# MAIN.net
KiCad netlist of a schematic drawn in Altium Designer
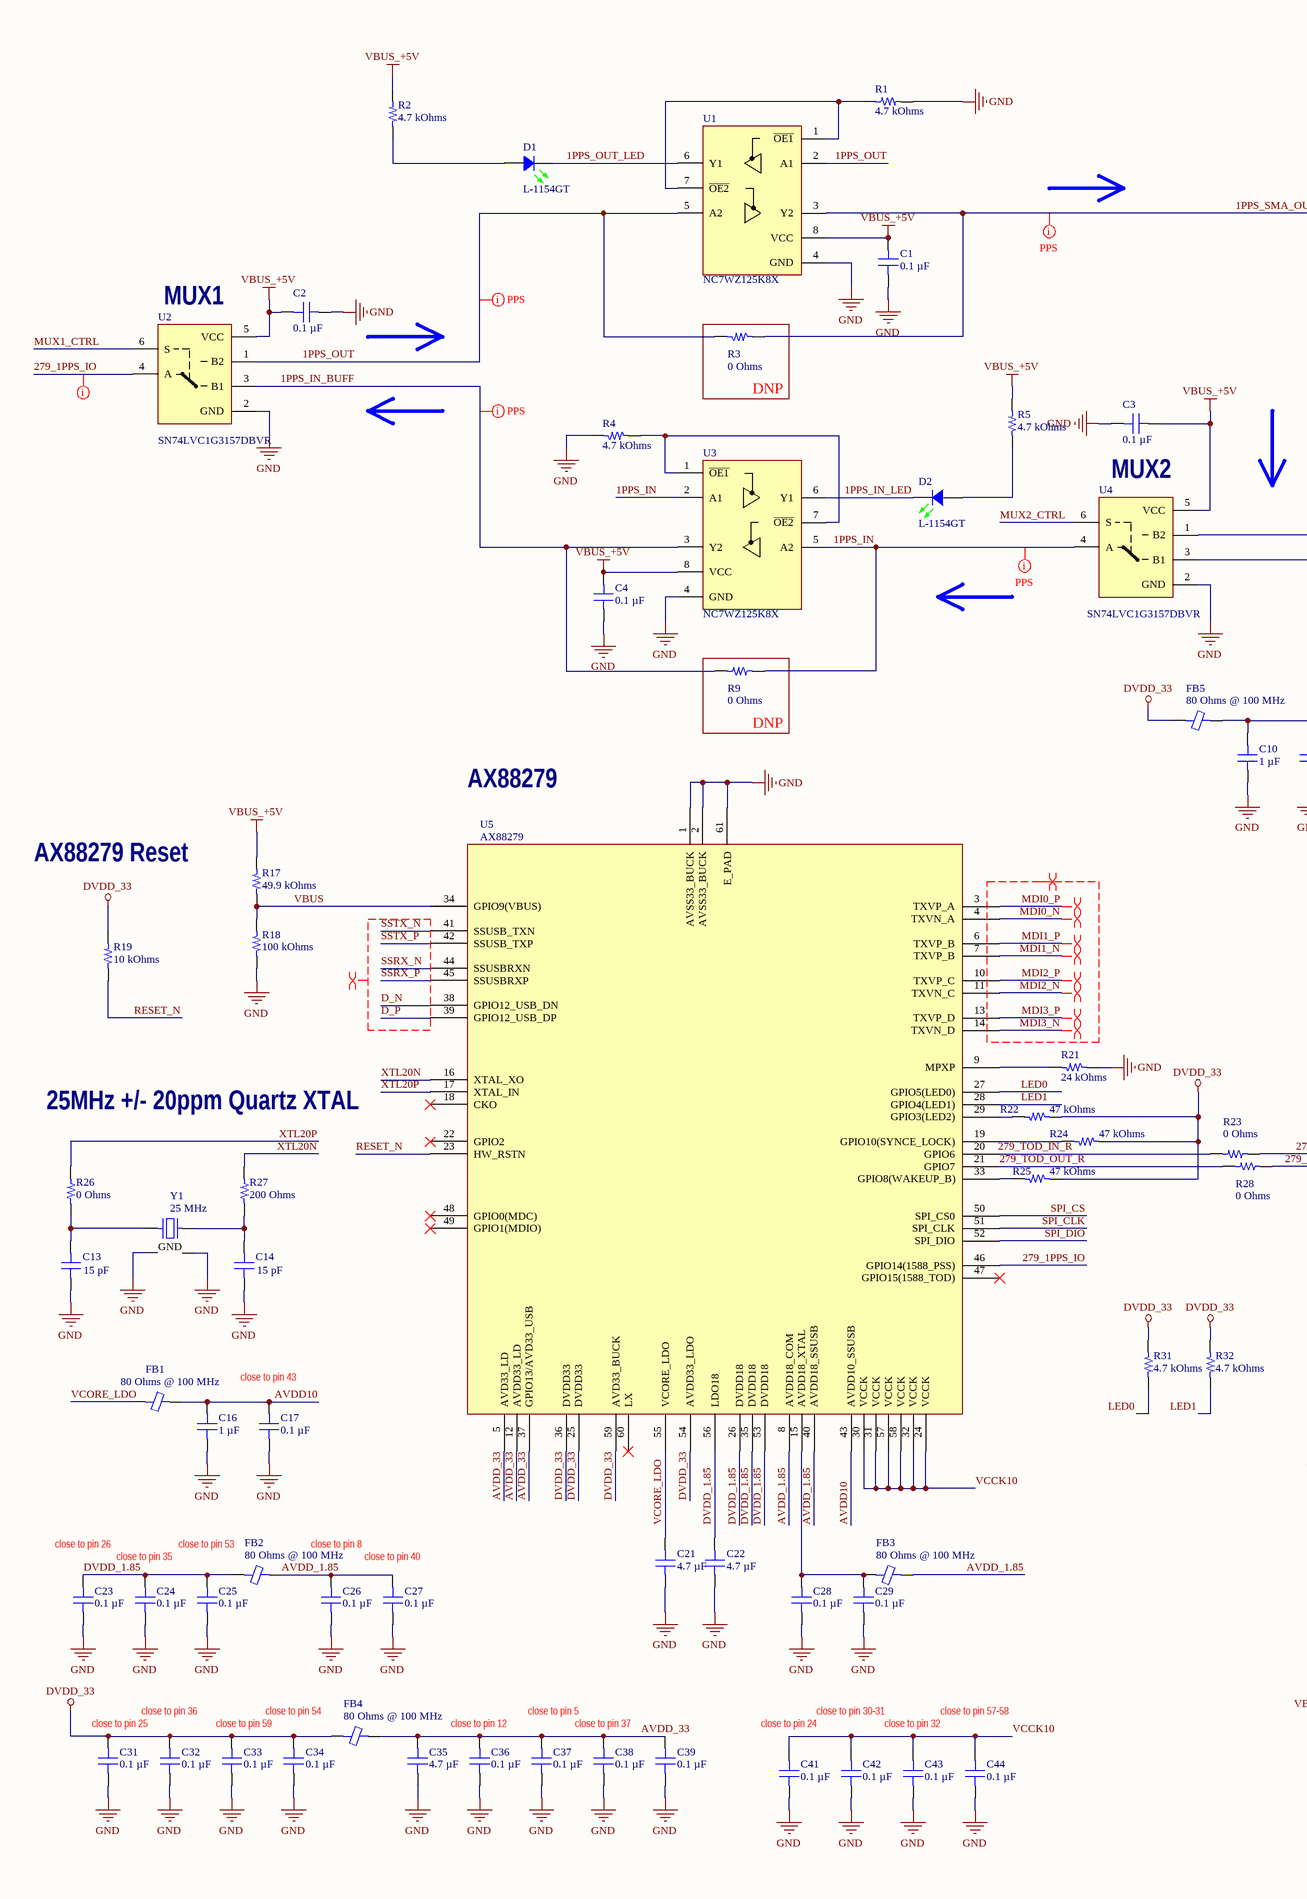
[diagram p0: MAIN.SchDoc, left]
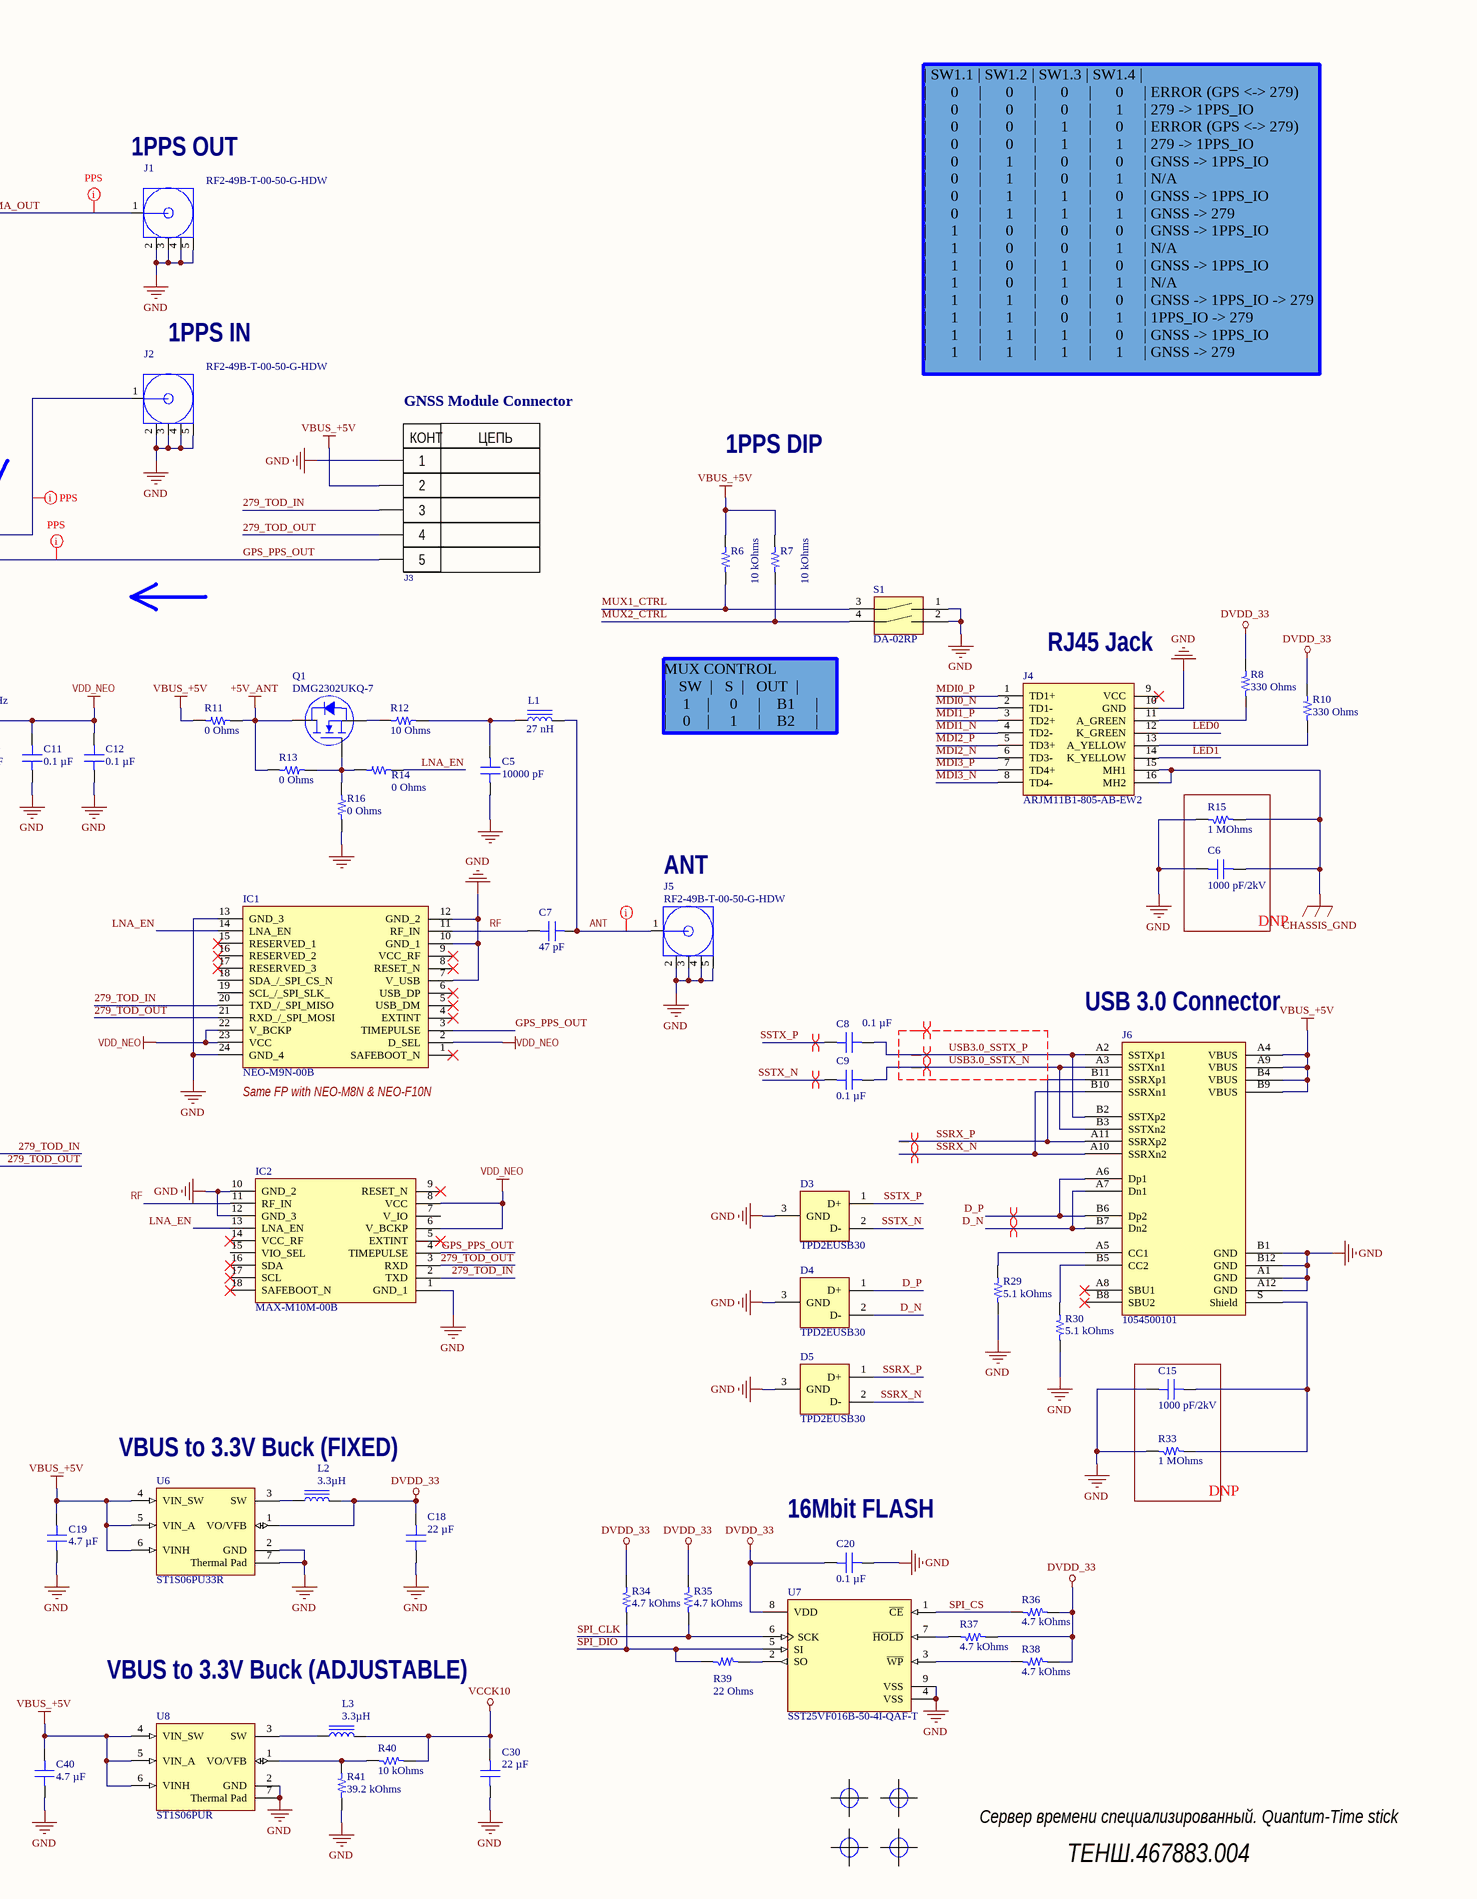
[diagram p1: MAIN.SchDoc, right]

(export (version "E")
  (design (tool "Eeschema 10.0.6"))
  (components
    (comp (ref "C1")
      (value "0.1 µF")
      (footprint "CAP 0402_1005")
      (description "CAP CER 0.1UF 10V X7R 0402")
      (fields (field (name "TOLERANCE") "±10%") (field (name "MANUFACTURER") "Yageo"))
      (libsource (lib "Celestial Altium Library - altium_library") (part "Capacitor"))
    )
    (comp (ref "C2")
      (value "0.1 µF")
      (footprint "CAP 0402_1005")
      (description "CAP CER 0.1UF 10V X7R 0402")
      (fields (field (name "TOLERANCE") "±10%") (field (name "MANUFACTURER") "Yageo"))
      (libsource (lib "Celestial Altium Library - altium_library") (part "Capacitor"))
    )
    (comp (ref "C3")
      (value "0.1 µF")
      (footprint "CAP 0402_1005")
      (description "CAP CER 0.1UF 10V X7R 0402")
      (fields (field (name "TOLERANCE") "±10%") (field (name "MANUFACTURER") "Yageo"))
      (libsource (lib "Celestial Altium Library - altium_library") (part "Capacitor"))
    )
    (comp (ref "C4")
      (value "0.1 µF")
      (footprint "CAP 0402_1005")
      (description "CAP CER 0.1UF 10V X7R 0402")
      (fields (field (name "TOLERANCE") "±10%") (field (name "MANUFACTURER") "Yageo"))
      (libsource (lib "Celestial Altium Library - altium_library") (part "Capacitor"))
    )
    (comp (ref "C5")
      (value "10000 pF")
      (footprint "CAP 0402_1005")
      (description "CAP CER 10000PF 50V X7R 0402")
      (fields (field (name "PART NUMBER") "CC0402KRX7R9BB103") (field (name "MANUFACTURER") "Yageo"))
      (libsource (lib "Celestial Altium Library - altium_library") (part "Capacitor"))
    )
    (comp (ref "C6")
      (value "1000 pF/2kV")
      (footprint "CAP 1206_3216 - 0.8MM")
      (description "CAP CER 1000PF 2KV X7R 1206")
      (fields (field (name "PART NUMBER") "CC1206KKX7RDBB102") (field (name "MANUFACTURER") "Yageo"))
      (libsource (lib "Celestial Altium Library - altium_library") (part "Capacitor"))
    )
    (comp (ref "C7")
      (value "47 pF")
      (footprint "CAP 0402_1005")
      (description "CAP CER 47PF 50V C0G/NPO 0402")
      (fields (field (name "MANUFACTURER") "Yageo") (field (name "TOLERANCE") "±10%"))
      (libsource (lib "Celestial Altium Library - altium_library") (part "Capacitor"))
    )
    (comp (ref "C8")
      (value "0.1 µF")
      (footprint "CAP 0402_1005")
      (description "CAP CER 0.1UF 10V X7R 0402")
      (fields (field (name "TOLERANCE") "±10%") (field (name "MANUFACTURER") "Yageo"))
      (libsource (lib "Celestial Altium Library - altium_library") (part "Capacitor"))
    )
    (comp (ref "C9")
      (value "0.1 µF")
      (footprint "CAP 0402_1005")
      (description "CAP CER 0.1UF 10V X7R 0402")
      (fields (field (name "TOLERANCE") "±10%") (field (name "MANUFACTURER") "Yageo"))
      (libsource (lib "Celestial Altium Library - altium_library") (part "Capacitor"))
    )
    (comp (ref "C10")
      (value "1 µF")
      (footprint "CAP 0402_1005")
      (description "CAP CER 1UF 10V X5R 0402")
      (fields (field (name "TOLERANCE") "±10%") (field (name "MANUFACTURER") "Yageo"))
      (libsource (lib "Celestial Altium Library - altium_library") (part "Capacitor"))
    )
    (comp (ref "C11")
      (value "0.1 µF")
      (footprint "CAP 0402_1005")
      (description "CAP CER 0.1UF 10V X7R 0402")
      (fields (field (name "TOLERANCE") "±10%") (field (name "MANUFACTURER") "Yageo"))
      (libsource (lib "Celestial Altium Library - altium_library") (part "Capacitor"))
    )
    (comp (ref "C12")
      (value "0.1 µF")
      (footprint "CAP 0402_1005")
      (description "CAP CER 0.1UF 10V X7R 0402")
      (fields (field (name "TOLERANCE") "±10%") (field (name "MANUFACTURER") "Yageo"))
      (libsource (lib "Celestial Altium Library - altium_library") (part "Capacitor"))
    )
    (comp (ref "C13")
      (value "15 pF")
      (footprint "CAP 0402_1005")
      (description "CAP CER 15PF 50V C0G/NPO 0402")
      (fields (field (name "MANUFACTURER") "Yageo") (field (name "TOLERANCE") "±10%"))
      (libsource (lib "Celestial Altium Library - altium_library") (part "Capacitor"))
    )
    (comp (ref "C14")
      (value "15 pF")
      (footprint "CAP 0402_1005")
      (description "CAP CER 15PF 50V C0G/NPO 0402")
      (fields (field (name "MANUFACTURER") "Yageo") (field (name "TOLERANCE") "±10%"))
      (libsource (lib "Celestial Altium Library - altium_library") (part "Capacitor"))
    )
    (comp (ref "C15")
      (value "1000 pF/2kV")
      (footprint "CAP 1206_3216 - 0.8MM")
      (description "CAP CER 1000PF 2KV X7R 1206")
      (fields (field (name "PART NUMBER") "CC1206KKX7RDBB102") (field (name "MANUFACTURER") "Yageo"))
      (libsource (lib "Celestial Altium Library - altium_library") (part "Capacitor"))
    )
    (comp (ref "C16")
      (value "1 µF")
      (footprint "CAP 0402_1005")
      (description "CAP CER 1UF 10V X5R 0402")
      (fields (field (name "TOLERANCE") "±10%") (field (name "MANUFACTURER") "Yageo"))
      (libsource (lib "Celestial Altium Library - altium_library") (part "Capacitor"))
    )
    (comp (ref "C17")
      (value "0.1 µF")
      (footprint "CAP 0402_1005")
      (description "CAP CER 0.1UF 10V X7R 0402")
      (fields (field (name "TOLERANCE") "±10%") (field (name "MANUFACTURER") "Yageo"))
      (libsource (lib "Celestial Altium Library - altium_library") (part "Capacitor"))
    )
    (comp (ref "C18")
      (value "22 µF")
      (footprint "CAP 0603_1608")
      (description "CAP CER 22UF 10V X5R 0603")
      (fields (field (name "MANUFACTURER") "Yageo") (field (name "TOLERANCE") "±20%"))
      (libsource (lib "Celestial Altium Library - altium_library") (part "Capacitor"))
    )
    (comp (ref "C19")
      (value "4.7 µF")
      (footprint "CAP 0402_1005")
      (description "CAP CER 4.7UF 10V X5R 0402")
      (fields (field (name "TOLERANCE") "±20%") (field (name "MANUFACTURER") "Yageo"))
      (libsource (lib "Celestial Altium Library - altium_library") (part "Capacitor"))
    )
    (comp (ref "C20")
      (value "0.1 µF")
      (footprint "CAP 0402_1005")
      (description "CAP CER 0.1UF 10V X7R 0402")
      (fields (field (name "TOLERANCE") "±10%") (field (name "MANUFACTURER") "Yageo"))
      (libsource (lib "Celestial Altium Library - altium_library") (part "Capacitor"))
    )
    (comp (ref "C21")
      (value "4.7 µF")
      (footprint "CAP 0402_1005")
      (description "CAP CER 4.7UF 10V X5R 0402")
      (fields (field (name "TOLERANCE") "±20%") (field (name "MANUFACTURER") "Yageo"))
      (libsource (lib "Celestial Altium Library - altium_library") (part "Capacitor"))
    )
    (comp (ref "C22")
      (value "4.7 µF")
      (footprint "CAP 0402_1005")
      (description "CAP CER 4.7UF 10V X5R 0402")
      (fields (field (name "TOLERANCE") "±20%") (field (name "MANUFACTURER") "Yageo"))
      (libsource (lib "Celestial Altium Library - altium_library") (part "Capacitor"))
    )
    (comp (ref "C23")
      (value "0.1 µF")
      (footprint "CAP 0402_1005")
      (description "CAP CER 0.1UF 10V X7R 0402")
      (fields (field (name "TOLERANCE") "±10%") (field (name "MANUFACTURER") "Yageo"))
      (libsource (lib "Celestial Altium Library - altium_library") (part "Capacitor"))
    )
    (comp (ref "C24")
      (value "0.1 µF")
      (footprint "CAP 0402_1005")
      (description "CAP CER 0.1UF 10V X7R 0402")
      (fields (field (name "TOLERANCE") "±10%") (field (name "MANUFACTURER") "Yageo"))
      (libsource (lib "Celestial Altium Library - altium_library") (part "Capacitor"))
    )
    (comp (ref "C25")
      (value "0.1 µF")
      (footprint "CAP 0402_1005")
      (description "CAP CER 0.1UF 10V X7R 0402")
      (fields (field (name "TOLERANCE") "±10%") (field (name "MANUFACTURER") "Yageo"))
      (libsource (lib "Celestial Altium Library - altium_library") (part "Capacitor"))
    )
    (comp (ref "C26")
      (value "0.1 µF")
      (footprint "CAP 0402_1005")
      (description "CAP CER 0.1UF 10V X7R 0402")
      (fields (field (name "TOLERANCE") "±10%") (field (name "MANUFACTURER") "Yageo"))
      (libsource (lib "Celestial Altium Library - altium_library") (part "Capacitor"))
    )
    (comp (ref "C27")
      (value "0.1 µF")
      (footprint "CAP 0402_1005")
      (description "CAP CER 0.1UF 10V X7R 0402")
      (fields (field (name "TOLERANCE") "±10%") (field (name "MANUFACTURER") "Yageo"))
      (libsource (lib "Celestial Altium Library - altium_library") (part "Capacitor"))
    )
    (comp (ref "C28")
      (value "0.1 µF")
      (footprint "CAP 0402_1005")
      (description "CAP CER 0.1UF 10V X7R 0402")
      (fields (field (name "TOLERANCE") "±10%") (field (name "MANUFACTURER") "Yageo"))
      (libsource (lib "Celestial Altium Library - altium_library") (part "Capacitor"))
    )
    (comp (ref "C29")
      (value "0.1 µF")
      (footprint "CAP 0402_1005")
      (description "CAP CER 0.1UF 10V X7R 0402")
      (fields (field (name "TOLERANCE") "±10%") (field (name "MANUFACTURER") "Yageo"))
      (libsource (lib "Celestial Altium Library - altium_library") (part "Capacitor"))
    )
    (comp (ref "C30")
      (value "22 µF")
      (footprint "CAP 0603_1608")
      (description "CAP CER 22UF 10V X5R 0603")
      (fields (field (name "MANUFACTURER") "Yageo") (field (name "TOLERANCE") "±20%"))
      (libsource (lib "Celestial Altium Library - altium_library") (part "Capacitor"))
    )
    (comp (ref "C31")
      (value "0.1 µF")
      (footprint "CAP 0402_1005")
      (description "CAP CER 0.1UF 10V X7R 0402")
      (fields (field (name "TOLERANCE") "±10%") (field (name "MANUFACTURER") "Yageo"))
      (libsource (lib "Celestial Altium Library - altium_library") (part "Capacitor"))
    )
    (comp (ref "C32")
      (value "0.1 µF")
      (footprint "CAP 0402_1005")
      (description "CAP CER 0.1UF 10V X7R 0402")
      (fields (field (name "TOLERANCE") "±10%") (field (name "MANUFACTURER") "Yageo"))
      (libsource (lib "Celestial Altium Library - altium_library") (part "Capacitor"))
    )
    (comp (ref "C33")
      (value "0.1 µF")
      (footprint "CAP 0402_1005")
      (description "CAP CER 0.1UF 10V X7R 0402")
      (fields (field (name "TOLERANCE") "±10%") (field (name "MANUFACTURER") "Yageo"))
      (libsource (lib "Celestial Altium Library - altium_library") (part "Capacitor"))
    )
    (comp (ref "C34")
      (value "0.1 µF")
      (footprint "CAP 0402_1005")
      (description "CAP CER 0.1UF 10V X7R 0402")
      (fields (field (name "TOLERANCE") "±10%") (field (name "MANUFACTURER") "Yageo"))
      (libsource (lib "Celestial Altium Library - altium_library") (part "Capacitor"))
    )
    (comp (ref "C35")
      (value "4.7 µF")
      (footprint "CAP 0402_1005")
      (description "CAP CER 4.7UF 10V X5R 0402")
      (fields (field (name "TOLERANCE") "±20%") (field (name "MANUFACTURER") "Yageo"))
      (libsource (lib "Celestial Altium Library - altium_library") (part "Capacitor"))
    )
    (comp (ref "C36")
      (value "0.1 µF")
      (footprint "CAP 0402_1005")
      (description "CAP CER 0.1UF 10V X7R 0402")
      (fields (field (name "TOLERANCE") "±10%") (field (name "MANUFACTURER") "Yageo"))
      (libsource (lib "Celestial Altium Library - altium_library") (part "Capacitor"))
    )
    (comp (ref "C37")
      (value "0.1 µF")
      (footprint "CAP 0402_1005")
      (description "CAP CER 0.1UF 10V X7R 0402")
      (fields (field (name "TOLERANCE") "±10%") (field (name "MANUFACTURER") "Yageo"))
      (libsource (lib "Celestial Altium Library - altium_library") (part "Capacitor"))
    )
    (comp (ref "C38")
      (value "0.1 µF")
      (footprint "CAP 0402_1005")
      (description "CAP CER 0.1UF 10V X7R 0402")
      (fields (field (name "TOLERANCE") "±10%") (field (name "MANUFACTURER") "Yageo"))
      (libsource (lib "Celestial Altium Library - altium_library") (part "Capacitor"))
    )
    (comp (ref "C39")
      (value "0.1 µF")
      (footprint "CAP 0402_1005")
      (description "CAP CER 0.1UF 10V X7R 0402")
      (fields (field (name "TOLERANCE") "±10%") (field (name "MANUFACTURER") "Yageo"))
      (libsource (lib "Celestial Altium Library - altium_library") (part "Capacitor"))
    )
    (comp (ref "C40")
      (value "4.7 µF")
      (footprint "CAP 0402_1005")
      (description "CAP CER 4.7UF 10V X5R 0402")
      (fields (field (name "TOLERANCE") "±20%") (field (name "MANUFACTURER") "Yageo"))
      (libsource (lib "Celestial Altium Library - altium_library") (part "Capacitor"))
    )
    (comp (ref "C41")
      (value "0.1 µF")
      (footprint "CAP 0402_1005")
      (description "CAP CER 0.1UF 10V X7R 0402")
      (fields (field (name "TOLERANCE") "±10%") (field (name "MANUFACTURER") "Yageo"))
      (libsource (lib "Celestial Altium Library - altium_library") (part "Capacitor"))
    )
    (comp (ref "C42")
      (value "0.1 µF")
      (footprint "CAP 0402_1005")
      (description "CAP CER 0.1UF 10V X7R 0402")
      (fields (field (name "TOLERANCE") "±10%") (field (name "MANUFACTURER") "Yageo"))
      (libsource (lib "Celestial Altium Library - altium_library") (part "Capacitor"))
    )
    (comp (ref "C43")
      (value "0.1 µF")
      (footprint "CAP 0402_1005")
      (description "CAP CER 0.1UF 10V X7R 0402")
      (fields (field (name "TOLERANCE") "±10%") (field (name "MANUFACTURER") "Yageo"))
      (libsource (lib "Celestial Altium Library - altium_library") (part "Capacitor"))
    )
    (comp (ref "C44")
      (value "0.1 µF")
      (footprint "CAP 0402_1005")
      (description "CAP CER 0.1UF 10V X7R 0402")
      (fields (field (name "TOLERANCE") "±10%") (field (name "MANUFACTURER") "Yageo"))
      (libsource (lib "Celestial Altium Library - altium_library") (part "Capacitor"))
    )
    (comp (ref "D1")
      (value "L-1154GT")
      (footprint "SamacSys:LED_3MM_GREEN")
      (description "LED, 3mm, Green")
      (libsource (lib "SamacSys") (part "L-1154GT"))
    )
    (comp (ref "D2")
      (value "L-1154GT")
      (footprint "SamacSys:LED_3MM_GREEN")
      (description "LED, 3mm, Green")
      (libsource (lib "SamacSys") (part "L-1154GT"))
    )
    (comp (ref "D3")
      (value "TPD2EUSB30")
      (footprint "SamacSys:SOT35P100X50-3N")
      (description "TVS DIODE 3.6VWM 8VC SOT3")
      (fields
        (field (name "MANUFACTURER_PART_NUMBER") "TPD2EUSB30ADRTR")
        (field (name "MOUSER PART NUMBER") "595-TPD2EUSB30ADRTR")
      )
      (libsource (lib "SamacSys") (part "TPD2EUSB30ADRTR"))
    )
    (comp (ref "D4")
      (value "TPD2EUSB30")
      (footprint "SamacSys:SOT35P100X50-3N")
      (description "TVS DIODE 3.6VWM 8VC SOT3")
      (fields
        (field (name "MANUFACTURER_PART_NUMBER") "TPD2EUSB30ADRTR")
        (field (name "MOUSER PART NUMBER") "595-TPD2EUSB30ADRTR")
      )
      (libsource (lib "SamacSys") (part "TPD2EUSB30ADRTR"))
    )
    (comp (ref "D5")
      (value "TPD2EUSB30")
      (footprint "SamacSys:SOT35P100X50-3N")
      (description "TVS DIODE 3.6VWM 8VC SOT3")
      (fields
        (field (name "MANUFACTURER_PART_NUMBER") "TPD2EUSB30ADRTR")
        (field (name "MOUSER PART NUMBER") "595-TPD2EUSB30ADRTR")
      )
      (libsource (lib "SamacSys") (part "TPD2EUSB30ADRTR"))
    )
    (comp (ref "FB1")
      (value "80 Ohms @ 100 MHz")
      (footprint "FER 0402_1005")
      (description "FERRITE BEAD 80 OHM 0402 1LN")
      (fields
        (field (name "MANUFACTURER") "Murata Electronics")
        (field (name "PART NUMBER") "BLM15PD800SN1D")
      )
      (libsource (lib "Celestial Altium Library - altium_library") (part "Ferrite Chip"))
    )
    (comp (ref "FB2")
      (value "80 Ohms @ 100 MHz")
      (footprint "FER 0402_1005")
      (description "FERRITE BEAD 80 OHM 0402 1LN")
      (fields
        (field (name "MANUFACTURER") "Murata Electronics")
        (field (name "PART NUMBER") "BLM15PD800SN1D")
      )
      (libsource (lib "Celestial Altium Library - altium_library") (part "Ferrite Chip"))
    )
    (comp (ref "FB3")
      (value "80 Ohms @ 100 MHz")
      (footprint "FER 0402_1005")
      (description "FERRITE BEAD 80 OHM 0402 1LN")
      (fields
        (field (name "MANUFACTURER") "Murata Electronics")
        (field (name "PART NUMBER") "BLM15PD800SN1D")
      )
      (libsource (lib "Celestial Altium Library - altium_library") (part "Ferrite Chip"))
    )
    (comp (ref "FB4")
      (value "80 Ohms @ 100 MHz")
      (footprint "FER 0402_1005")
      (description "FERRITE BEAD 80 OHM 0402 1LN")
      (fields
        (field (name "MANUFACTURER") "Murata Electronics")
        (field (name "PART NUMBER") "BLM15PD800SN1D")
      )
      (libsource (lib "Celestial Altium Library - altium_library") (part "Ferrite Chip"))
    )
    (comp (ref "FB5")
      (value "80 Ohms @ 100 MHz")
      (footprint "FER 0402_1005")
      (description "FERRITE BEAD 80 OHM 0402 1LN")
      (fields
        (field (name "MANUFACTURER") "Murata Electronics")
        (field (name "PART NUMBER") "BLM15PD800SN1D")
      )
      (libsource (lib "Celestial Altium Library - altium_library") (part "Ferrite Chip"))
    )
    (comp (ref "IC1")
      (value "NEO-M9N-00B")
      (footprint "SamacSys:NEOM9N00B")
      (description "Integrated Circuit")
      (fields (field (name "MOUSER PART NUMBER") "377-NEO-M9N-00B"))
      (libsource (lib "SamacSys") (part "NEO-M9N-00B"))
    )
    (comp (ref "IC2")
      (value "MAX-M10M-00B")
      (footprint "MAXM10M00B")
      (description "Integrated Circuit")
      (fields (field (name "MOUSER PART NUMBER") "377-MAX-M10M-00B"))
      (libsource (lib "SamacSys") (part "MAX-M10M-00B"))
    )
    (comp (ref "J1")
      (value "RF2-49B-T-00-50-G-HDW")
      (footprint "SamacSys:RF249BT0050GHDW")
      (description "Connector")
      (libsource (lib "SamacSys") (part "RF2-49B-T-00-50-G-HDW"))
    )
    (comp (ref "J2")
      (value "RF2-49B-T-00-50-G-HDW")
      (footprint "SamacSys:RF249BT0050GHDW")
      (description "Connector")
      (libsource (lib "SamacSys") (part "RF2-49B-T-00-50-G-HDW"))
    )
    (comp (ref "J3")
      (value "PBS-5")
      (footprint "SamacSys:PBS-5")
      (description "Connector")
      (fields (field (name "MANUFACTURER") "Connfly") (field (name "PART NUMBER") "PBD-5"))
      (libsource (lib "SamacSys") (part "PBS-5"))
    )
    (comp (ref "J4")
      (value "ARJM11B1-805-AB-EW2")
      (footprint "SamacSys:ARJM11B1805ABEW2")
      (description "Connector")
      (fields (field (name "MOUSER PART NUMBER") "815-RJM11B1805ABEW2"))
      (libsource (lib "SamacSys") (part "ARJM11B1-805-AB-EW2"))
    )
    (comp (ref "J5")
      (value "RF2-49B-T-00-50-G-HDW")
      (footprint "SamacSys:RF249BT0050GHDW")
      (description "Connector")
      (libsource (lib "SamacSys") (part "RF2-49B-T-00-50-G-HDW"))
    )
    (comp (ref "J6")
      (value "1054500101")
      (footprint "Molex 1054500101")
      (description "CONN RCP USB3.1 TYPEC 24P SMD RA")
      (fields (field (name "MANUFACTURER") "Molex"))
      (libsource (lib "Celestial Altium Library - altium_library") (part "USB 3.0 Type C"))
    )
    (comp (ref "L1")
      (value "27 nH")
      (footprint "Murata LQG15 0402")
      (description "FIXED IND 27NH 350MA 0.46OHM SMD")
      (fields
        (field (name "PART NUMBER") "LQG15HS27NJ02D")
        (field (name "MANUFACTURER") "Murata Electronics")
      )
      (libsource (lib "Celestial Altium Library - altium_library") (part "Inductor"))
    )
    (comp (ref "L2")
      (value "3.3µH")
      (footprint "IND 1008_2520")
      (description "FIXED IND 3.3UH 1.2A 100 MOHM")
      (fields (field (name "TOLERANCE") "±20%") (field (name "MANUFACTURER") "Murata Electronics"))
      (libsource (lib "Celestial Altium Library - altium_library") (part "Inductor"))
    )
    (comp (ref "L3")
      (value "3.3µH")
      (footprint "IND 1008_2520")
      (description "FIXED IND 3.3UH 1.2A 100 MOHM")
      (fields (field (name "TOLERANCE") "±20%") (field (name "MANUFACTURER") "Murata Electronics"))
      (libsource (lib "Celestial Altium Library - altium_library") (part "Inductor"))
    )
    (comp (ref "MNT1")
      (value "MOUNT_HOLE")
      (footprint "SamacSys:MOUNT_3mm")
      (description "Mount hole")
      (libsource (lib "SamacSys") (part "MOUNT_HOLE"))
    )
    (comp (ref "MNT2")
      (value "MOUNT_HOLE")
      (footprint "SamacSys:MOUNT_3mm")
      (description "Mount hole")
      (libsource (lib "SamacSys") (part "MOUNT_HOLE"))
    )
    (comp (ref "MNT3")
      (value "MOUNT_HOLE")
      (footprint "SamacSys:MOUNT_3mm")
      (description "Mount hole")
      (libsource (lib "SamacSys") (part "MOUNT_HOLE"))
    )
    (comp (ref "MNT4")
      (value "MOUNT_HOLE")
      (footprint "SamacSys:MOUNT_3mm")
      (description "Mount hole")
      (libsource (lib "SamacSys") (part "MOUNT_HOLE"))
    )
    (comp (ref "Q1")
      (value "DMG2302UKQ-7")
      (footprint "DIODES SOT-23-3")
      (description "MOSFET BVDSS: 8V-24V SOT23 T&R 3")
      (fields (field (name "MANUFACTURER") "Diodes Incorporated"))
      (libsource (lib "Celestial Altium Library - altium_library") (part "DIODES INC MOSFET N-CH SOT-23-3"))
    )
    (comp (ref "R1")
      (value "4.7 kOhms")
      (footprint "YAGEO RES 0402_1005")
      (description "RES 4.7K OHM 1% 1/16W 0402")
      (fields (field (name "TOLERANCE") "±1%") (field (name "MANUFACTURER") "Yageo"))
      (libsource (lib "Celestial Altium Library - altium_library") (part "Resistor"))
    )
    (comp (ref "R2")
      (value "4.7 kOhms")
      (footprint "YAGEO RES 0402_1005")
      (description "RES 4.7K OHM 1% 1/16W 0402")
      (fields (field (name "TOLERANCE") "±1%") (field (name "MANUFACTURER") "Yageo"))
      (libsource (lib "Celestial Altium Library - altium_library") (part "Resistor"))
    )
    (comp (ref "R3")
      (value "0 Ohms")
      (footprint "YAGEO RES 0402_1005")
      (description "RES 0 OHM JUMPER 1/16W 0402")
      (fields (field (name "TOLERANCE") "Jumper") (field (name "MANUFACTURER") "Yageo"))
      (libsource (lib "Celestial Altium Library - altium_library") (part "Resistor"))
    )
    (comp (ref "R4")
      (value "4.7 kOhms")
      (footprint "YAGEO RES 0402_1005")
      (description "RES 4.7K OHM 1% 1/16W 0402")
      (fields (field (name "TOLERANCE") "±1%") (field (name "MANUFACTURER") "Yageo"))
      (libsource (lib "Celestial Altium Library - altium_library") (part "Resistor"))
    )
    (comp (ref "R5")
      (value "4.7 kOhms")
      (footprint "YAGEO RES 0402_1005")
      (description "RES 4.7K OHM 1% 1/16W 0402")
      (fields (field (name "TOLERANCE") "±1%") (field (name "MANUFACTURER") "Yageo"))
      (libsource (lib "Celestial Altium Library - altium_library") (part "Resistor"))
    )
    (comp (ref "R6")
      (value "10 kOhms")
      (footprint "YAGEO RES 0402_1005")
      (description "RES 10K OHM 1% 1/16W 0402")
      (fields (field (name "TOLERANCE") "±1%") (field (name "MANUFACTURER") "Yageo"))
      (libsource (lib "Celestial Altium Library - altium_library") (part "Resistor"))
    )
    (comp (ref "R7")
      (value "10 kOhms")
      (footprint "YAGEO RES 0402_1005")
      (description "RES 10K OHM 1% 1/16W 0402")
      (fields (field (name "TOLERANCE") "±1%") (field (name "MANUFACTURER") "Yageo"))
      (libsource (lib "Celestial Altium Library - altium_library") (part "Resistor"))
    )
    (comp (ref "R8")
      (value "330 Ohms")
      (footprint "YAGEO RES 0402_1005")
      (description "RES 330 OHM 1% 1/16W 0402")
      (fields (field (name "TOLERANCE") "±1%") (field (name "MANUFACTURER") "Yageo"))
      (libsource (lib "Celestial Altium Library - altium_library") (part "Resistor"))
    )
    (comp (ref "R9")
      (value "0 Ohms")
      (footprint "YAGEO RES 0402_1005")
      (description "RES 0 OHM JUMPER 1/16W 0402")
      (fields (field (name "TOLERANCE") "Jumper") (field (name "MANUFACTURER") "Yageo"))
      (libsource (lib "Celestial Altium Library - altium_library") (part "Resistor"))
    )
    (comp (ref "R10")
      (value "330 Ohms")
      (footprint "YAGEO RES 0402_1005")
      (description "RES 330 OHM 1% 1/16W 0402")
      (fields (field (name "TOLERANCE") "±1%") (field (name "MANUFACTURER") "Yageo"))
      (libsource (lib "Celestial Altium Library - altium_library") (part "Resistor"))
    )
    (comp (ref "R11")
      (value "0 Ohms")
      (footprint "YAGEO RES 0402_1005")
      (description "RES 0 OHM JUMPER 1/16W 0402")
      (fields (field (name "TOLERANCE") "Jumper") (field (name "MANUFACTURER") "Yageo"))
      (libsource (lib "Celestial Altium Library - altium_library") (part "Resistor"))
    )
    (comp (ref "R12")
      (value "10 Ohms")
      (footprint "YAGEO RES 0603_1608")
      (description "RES 10 OHM 1% 1/10W 0603")
      (fields (field (name "PART NUMBER") "RC0603FR-0710RL") (field (name "MANUFACTURER") "Yageo"))
      (libsource (lib "Celestial Altium Library - altium_library") (part "Resistor"))
    )
    (comp (ref "R13")
      (value "0 Ohms")
      (footprint "YAGEO RES 0402_1005")
      (description "RES 0 OHM JUMPER 1/16W 0402")
      (fields (field (name "TOLERANCE") "Jumper") (field (name "MANUFACTURER") "Yageo"))
      (libsource (lib "Celestial Altium Library - altium_library") (part "Resistor"))
    )
    (comp (ref "R14")
      (value "0 Ohms")
      (footprint "YAGEO RES 0402_1005")
      (description "RES 0 OHM JUMPER 1/16W 0402")
      (fields (field (name "TOLERANCE") "Jumper") (field (name "MANUFACTURER") "Yageo"))
      (libsource (lib "Celestial Altium Library - altium_library") (part "Resistor"))
    )
    (comp (ref "R15")
      (value "1 MOhms")
      (footprint "YAGEO RES 0402_1005")
      (description "RES 1M OHM 1% 1/16W 0402")
      (fields (field (name "TOLERANCE") "±1%") (field (name "MANUFACTURER") "Yageo"))
      (libsource (lib "Celestial Altium Library - altium_library") (part "Resistor"))
    )
    (comp (ref "R16")
      (value "0 Ohms")
      (footprint "YAGEO RES 0402_1005")
      (description "RES 0 OHM JUMPER 1/16W 0402")
      (fields (field (name "TOLERANCE") "Jumper") (field (name "MANUFACTURER") "Yageo"))
      (libsource (lib "Celestial Altium Library - altium_library") (part "Resistor"))
    )
    (comp (ref "R17")
      (value "49.9 kOhms")
      (footprint "YAGEO RES 0402_1005")
      (description "RES 49.9K OHM 1% 1/16W 0402")
      (fields (field (name "TOLERANCE") "±1%") (field (name "MANUFACTURER") "Yageo"))
      (libsource (lib "Celestial Altium Library - altium_library") (part "Resistor"))
    )
    (comp (ref "R18")
      (value "100 kOhms")
      (footprint "YAGEO RES 0402_1005")
      (description "RES 100K OHM 1% 1/16W 0402")
      (fields (field (name "TOLERANCE") "±1%") (field (name "MANUFACTURER") "Yageo"))
      (libsource (lib "Celestial Altium Library - altium_library") (part "Resistor"))
    )
    (comp (ref "R19")
      (value "10 kOhms")
      (footprint "YAGEO RES 0402_1005")
      (description "RES 10K OHM 1% 1/16W 0402")
      (fields (field (name "TOLERANCE") "±1%") (field (name "MANUFACTURER") "Yageo"))
      (libsource (lib "Celestial Altium Library - altium_library") (part "Resistor"))
    )
    (comp (ref "R21")
      (value "24 kOhms")
      (footprint "YAGEO RES 0402_1005")
      (description "RES 24K OHM 1% 1/16W 0402")
      (fields (field (name "TOLERANCE") "±1%") (field (name "MANUFACTURER") "Yageo"))
      (libsource (lib "Celestial Altium Library - altium_library") (part "Resistor"))
    )
    (comp (ref "R22")
      (value "47 kOhms")
      (footprint "YAGEO RES 0402_1005")
      (description "RES 47K OHM 1% 1/16W 0402")
      (fields (field (name "TOLERANCE") "±1%") (field (name "MANUFACTURER") "Yageo"))
      (libsource (lib "Celestial Altium Library - altium_library") (part "Resistor"))
    )
    (comp (ref "R23")
      (value "0 Ohms")
      (footprint "YAGEO RES 0402_1005")
      (description "RES 0 OHM JUMPER 1/16W 0402")
      (fields (field (name "TOLERANCE") "Jumper") (field (name "MANUFACTURER") "Yageo"))
      (libsource (lib "Celestial Altium Library - altium_library") (part "Resistor"))
    )
    (comp (ref "R24")
      (value "47 kOhms")
      (footprint "YAGEO RES 0402_1005")
      (description "RES 47K OHM 1% 1/16W 0402")
      (fields (field (name "TOLERANCE") "±1%") (field (name "MANUFACTURER") "Yageo"))
      (libsource (lib "Celestial Altium Library - altium_library") (part "Resistor"))
    )
    (comp (ref "R25")
      (value "47 kOhms")
      (footprint "YAGEO RES 0402_1005")
      (description "RES 47K OHM 1% 1/16W 0402")
      (fields (field (name "TOLERANCE") "±1%") (field (name "MANUFACTURER") "Yageo"))
      (libsource (lib "Celestial Altium Library - altium_library") (part "Resistor"))
    )
    (comp (ref "R26")
      (value "0 Ohms")
      (footprint "YAGEO RES 0402_1005")
      (description "RES 0 OHM JUMPER 1/16W 0402")
      (fields (field (name "TOLERANCE") "Jumper") (field (name "MANUFACTURER") "Yageo"))
      (libsource (lib "Celestial Altium Library - altium_library") (part "Resistor"))
    )
    (comp (ref "R27")
      (value "200 Ohms")
      (footprint "YAGEO RES 0402_1005")
      (description "RES 200 OHM 1% 1/16W 0402")
      (fields (field (name "MANUFACTURER") "Yageo") (field (name "PART NUMBER") "RC0402FR-07200RL"))
      (libsource (lib "Celestial Altium Library - altium_library") (part "Resistor"))
    )
    (comp (ref "R28")
      (value "0 Ohms")
      (footprint "YAGEO RES 0402_1005")
      (description "RES 0 OHM JUMPER 1/16W 0402")
      (fields (field (name "TOLERANCE") "Jumper") (field (name "MANUFACTURER") "Yageo"))
      (libsource (lib "Celestial Altium Library - altium_library") (part "Resistor"))
    )
    (comp (ref "R29")
      (value "5.1 kOhms")
      (footprint "YAGEO RES 0402_1005")
      (description "RES 5.1K OHM 1% 1/16W 0402")
      (fields (field (name "TOLERANCE") "±1%") (field (name "MANUFACTURER") "Yageo"))
      (libsource (lib "Celestial Altium Library - altium_library") (part "Resistor"))
    )
    (comp (ref "R30")
      (value "5.1 kOhms")
      (footprint "YAGEO RES 0402_1005")
      (description "RES 5.1K OHM 1% 1/16W 0402")
      (fields (field (name "TOLERANCE") "±1%") (field (name "MANUFACTURER") "Yageo"))
      (libsource (lib "Celestial Altium Library - altium_library") (part "Resistor"))
    )
    (comp (ref "R31")
      (value "4.7 kOhms")
      (footprint "YAGEO RES 0402_1005")
      (description "RES 4.7K OHM 1% 1/16W 0402")
      (fields (field (name "TOLERANCE") "±1%") (field (name "MANUFACTURER") "Yageo"))
      (libsource (lib "Celestial Altium Library - altium_library") (part "Resistor"))
    )
    (comp (ref "R32")
      (value "4.7 kOhms")
      (footprint "YAGEO RES 0402_1005")
      (description "RES 4.7K OHM 1% 1/16W 0402")
      (fields (field (name "TOLERANCE") "±1%") (field (name "MANUFACTURER") "Yageo"))
      (libsource (lib "Celestial Altium Library - altium_library") (part "Resistor"))
    )
    (comp (ref "R33")
      (value "1 MOhms")
      (footprint "YAGEO RES 0402_1005")
      (description "RES 1M OHM 1% 1/16W 0402")
      (fields (field (name "TOLERANCE") "±1%") (field (name "MANUFACTURER") "Yageo"))
      (libsource (lib "Celestial Altium Library - altium_library") (part "Resistor"))
    )
    (comp (ref "R34")
      (value "4.7 kOhms")
      (footprint "YAGEO RES 0402_1005")
      (description "RES 4.7K OHM 1% 1/16W 0402")
      (fields (field (name "TOLERANCE") "±1%") (field (name "MANUFACTURER") "Yageo"))
      (libsource (lib "Celestial Altium Library - altium_library") (part "Resistor"))
    )
    (comp (ref "R35")
      (value "4.7 kOhms")
      (footprint "YAGEO RES 0402_1005")
      (description "RES 4.7K OHM 1% 1/16W 0402")
      (fields (field (name "TOLERANCE") "±1%") (field (name "MANUFACTURER") "Yageo"))
      (libsource (lib "Celestial Altium Library - altium_library") (part "Resistor"))
    )
    (comp (ref "R36")
      (value "4.7 kOhms")
      (footprint "YAGEO RES 0402_1005")
      (description "RES 4.7K OHM 1% 1/16W 0402")
      (fields (field (name "TOLERANCE") "±1%") (field (name "MANUFACTURER") "Yageo"))
      (libsource (lib "Celestial Altium Library - altium_library") (part "Resistor"))
    )
    (comp (ref "R37")
      (value "4.7 kOhms")
      (footprint "YAGEO RES 0402_1005")
      (description "RES 4.7K OHM 1% 1/16W 0402")
      (fields (field (name "TOLERANCE") "±1%") (field (name "MANUFACTURER") "Yageo"))
      (libsource (lib "Celestial Altium Library - altium_library") (part "Resistor"))
    )
    (comp (ref "R38")
      (value "4.7 kOhms")
      (footprint "YAGEO RES 0402_1005")
      (description "RES 4.7K OHM 1% 1/16W 0402")
      (fields (field (name "TOLERANCE") "±1%") (field (name "MANUFACTURER") "Yageo"))
      (libsource (lib "Celestial Altium Library - altium_library") (part "Resistor"))
    )
    (comp (ref "R39")
      (value "22 Ohms")
      (footprint "YAGEO RES 0402_1005")
      (description "RES 22 OHM 1% 1/16W 0402")
      (fields (field (name "TOLERANCE") "±1%") (field (name "MANUFACTURER") "Yageo"))
      (libsource (lib "Celestial Altium Library - altium_library") (part "Resistor"))
    )
    (comp (ref "R40")
      (value "10 kOhms")
      (footprint "YAGEO RES 0402_1005")
      (description "RES 10K OHM 1% 1/16W 0402")
      (fields (field (name "TOLERANCE") "±1%") (field (name "MANUFACTURER") "Yageo"))
      (libsource (lib "Celestial Altium Library - altium_library") (part "Resistor"))
    )
    (comp (ref "R41")
      (value "39.2 kOhms")
      (footprint "YAGEO RES 0402_1005")
      (description "RES 39.2K OHM 1% 1/16W 0402")
      (fields (field (name "TOLERANCE") "±1%") (field (name "MANUFACTURER") "Yageo"))
      (libsource (lib "Celestial Altium Library - altium_library") (part "Resistor"))
    )
    (comp (ref "S1")
      (value "DA-02RP")
      (footprint "SamacSys:DA02RP")
      (description "DIP Switch, 2P")
      (libsource (lib "SamacSys") (part "DA-02RP"))
    )
    (comp (ref "U1")
      (value "NC7WZ125K8X")
      (footprint "SamacSys:SOP50P310X90-8N")
      (description "Integrated Circuit")
      (libsource (lib "") (part "NC7WZ125K8X_1"))
    )
    (comp (ref "U2")
      (value "SN74LVC1G3157DBVR")
      (footprint "SamacSys:SOT95P280X145-6N")
      (description "Integrated Circuit")
      (fields (field (name "MOUSER PART NUMBER") "595-SN74LVC1G3157DBV"))
      (libsource (lib "SamacSys") (part "SN74LVC1G3157DBVR"))
    )
    (comp (ref "U3")
      (value "NC7WZ125K8X")
      (footprint "SamacSys:SOP50P310X90-8N")
      (description "Integrated Circuit")
      (libsource (lib "SamacSys") (part "NC7WZ125K8X"))
    )
    (comp (ref "U4")
      (value "SN74LVC1G3157DBVR")
      (footprint "SamacSys:SOT95P280X145-6N")
      (description "Integrated Circuit")
      (fields (field (name "MOUSER PART NUMBER") "595-SN74LVC1G3157DBV"))
      (libsource (lib "SamacSys") (part "SN74LVC1G3157DBVR"))
    )
    (comp (ref "U5")
      (value "AX88279")
      (footprint "IC_AX88279")
      (libsource (lib "LotusSound") (part "IC_AX88279"))
    )
    (comp (ref "U6")
      (value "ST1S06PU33R")
      (footprint "DFN6D_L")
      (fields (field (name "MANUFACTURER") "STMicroelectronics"))
      (libsource (lib "Altium Content Vault") (part "PM-DCDC-ST1S06-IL7"))
    )
    (comp (ref "U7")
      (value "SST25VF016B-50-4I-QAF-T")
      (footprint "FP-C04-452-MFG")
      (libsource (lib "Altium Content Vault") (part "d7313dde12fd16fde488169701056cc"))
    )
    (comp (ref "U8")
      (value "ST1S06PUR")
      (footprint "DFN6D_M")
      (libsource (lib "Altium Content Vault") (part "PM-DCDC-ST1S06-IL7"))
    )
    (comp (ref "Y1")
      (value "25 MHz")
      (footprint "NDK NX3225GA")
      (description "CRYSTAL 25.0000MHZ 8PF SMD")
      (fields
        (field (name "MANUFACTURER") "NDK America, Inc.")
        (field (name "PART NUMBER") "NX3225GA-25.000M-STD-CRG-2")
      )
      (libsource (lib "Celestial Altium Library - altium_library") (part "NDK Crystal NX3225GA"))
    )
  )
  (nets
    (net (code "1") (name "+5V_ANT") (class "Default")
      (node (ref "Q1") (pin "3") (pinfunction "D_3") (pintype "passive"))
      (node (ref "R11") (pin "1") (pinfunction "1_1") (pintype "passive"))
      (node (ref "R13") (pin "2") (pinfunction "2_2") (pintype "passive"))
    )
    (net (code "2") (name "/1PPS_IN") (class "Default")
      (node (ref "R9") (pin "1") (pinfunction "1_1") (pintype "passive"))
      (node (ref "U3") (pin "2") (pinfunction "A1_2") (pintype "passive"))
      (node (ref "U3") (pin "5") (pinfunction "A2_5") (pintype "passive"))
      (node (ref "U4") (pin "4") (pinfunction "A_4") (pintype "passive"))
    )
    (net (code "3") (name "/1PPS_IN_BUFF") (class "Default")
      (node (ref "R9") (pin "2") (pinfunction "2_2") (pintype "passive"))
      (node (ref "U2") (pin "3") (pinfunction "B1_3") (pintype "passive"))
      (node (ref "U3") (pin "3") (pinfunction "Y2_3") (pintype "passive"))
    )
    (net (code "4") (name "/1PPS_IN_LED") (class "Default")
      (node (ref "D2") (pin "C") (pinfunction "C_C") (pintype "passive"))
      (node (ref "U3") (pin "6") (pinfunction "Y1_6") (pintype "passive"))
    )
    (net (code "5") (name "/1PPS_OUT") (class "Default")
      (node (ref "R3") (pin "2") (pinfunction "2_2") (pintype "passive"))
      (node (ref "U1") (pin "2") (pinfunction "A1_2") (pintype "passive"))
      (node (ref "U1") (pin "5") (pinfunction "A2_5") (pintype "passive"))
      (node (ref "U2") (pin "1") (pinfunction "B2_1") (pintype "passive"))
    )
    (net (code "6") (name "/1PPS_OUT_LED") (class "Default")
      (node (ref "D1") (pin "C") (pinfunction "C_C") (pintype "passive"))
      (node (ref "U1") (pin "6") (pinfunction "Y1_6") (pintype "passive"))
    )
    (net (code "7") (name "/1PPS_SMA_OUT") (class "Default")
      (node (ref "J1") (pin "1") (pinfunction "1_1") (pintype "passive"))
      (node (ref "R3") (pin "1") (pinfunction "1_1") (pintype "passive"))
      (node (ref "U1") (pin "3") (pinfunction "Y2_3") (pintype "passive"))
    )
    (net (code "8") (name "/279_1PPS_IO") (class "Default")
      (node (ref "U2") (pin "4") (pinfunction "A_4") (pintype "passive"))
      (node (ref "U5") (pin "46") (pinfunction "GPIO14(1588_PSS)_46") (pintype "passive"))
    )
    (net (code "9") (name "/279_TOD_IN") (class "Default")
      (node (ref "IC1") (pin "20") (pinfunction "TXD_/_SPI_MISO_20") (pintype "passive"))
      (node (ref "IC2") (pin "2") (pinfunction "TXD_2") (pintype "passive"))
      (node (ref "J3") (pin "3") (pinfunction "3_3") (pintype "passive"))
      (node (ref "R23") (pin "1") (pinfunction "1_1") (pintype "passive"))
    )
    (net (code "10") (name "/279_TOD_IN_R") (class "Default")
      (node (ref "R23") (pin "2") (pinfunction "2_2") (pintype "passive"))
      (node (ref "U5") (pin "20") (pinfunction "GPIO6_20") (pintype "passive"))
    )
    (net (code "11") (name "/279_TOD_OUT") (class "Default")
      (node (ref "IC1") (pin "21") (pinfunction "RXD_/_SPI_MOSI_21") (pintype "passive"))
      (node (ref "IC2") (pin "3") (pinfunction "RXD_3") (pintype "passive"))
      (node (ref "J3") (pin "4") (pinfunction "4_4") (pintype "passive"))
      (node (ref "R28") (pin "1") (pinfunction "1_1") (pintype "passive"))
    )
    (net (code "12") (name "/279_TOD_OUT_R") (class "Default")
      (node (ref "R28") (pin "2") (pinfunction "2_2") (pintype "passive"))
      (node (ref "U5") (pin "21") (pinfunction "GPIO7_21") (pintype "passive"))
    )
    (net (code "13") (name "/ANT") (class "Default")
      (node (ref "C7") (pin "1") (pinfunction "1_1") (pintype "passive"))
      (node (ref "J5") (pin "1") (pinfunction "1_1") (pintype "passive"))
      (node (ref "L1") (pin "2") (pinfunction "2_2") (pintype "passive"))
    )
    (net (code "14") (name "/AVDD10") (class "Default")
      (node (ref "C16") (pin "2") (pinfunction "2_2") (pintype "passive"))
      (node (ref "C17") (pin "2") (pinfunction "2_2") (pintype "passive"))
      (node (ref "FB1") (pin "2") (pinfunction "2_2") (pintype "passive"))
      (node (ref "U5") (pin "43") (pinfunction "AVDD10_SSUSB_43") (pintype "passive"))
    )
    (net (code "15") (name "/AVDD_1.85") (class "Default")
      (node (ref "C26") (pin "2") (pinfunction "2_2") (pintype "passive"))
      (node (ref "C27") (pin "2") (pinfunction "2_2") (pintype "passive"))
      (node (ref "FB2") (pin "2") (pinfunction "2_2") (pintype "passive"))
      (node (ref "FB3") (pin "2") (pinfunction "2_2") (pintype "passive"))
      (node (ref "U5") (pin "40") (pinfunction "AVDD18_SSUSB_40") (pintype "passive"))
      (node (ref "U5") (pin "8") (pinfunction "AVDD18_COM_8") (pintype "passive"))
    )
    (net (code "16") (name "/AVDD_33") (class "Default")
      (node (ref "C35") (pin "2") (pinfunction "2_2") (pintype "passive"))
      (node (ref "C36") (pin "2") (pinfunction "2_2") (pintype "passive"))
      (node (ref "C37") (pin "2") (pinfunction "2_2") (pintype "passive"))
      (node (ref "C38") (pin "2") (pinfunction "2_2") (pintype "passive"))
      (node (ref "C39") (pin "2") (pinfunction "2_2") (pintype "passive"))
      (node (ref "FB4") (pin "2") (pinfunction "2_2") (pintype "passive"))
      (node (ref "U5") (pin "12") (pinfunction "AVDD33_LD_12") (pintype "passive"))
      (node (ref "U5") (pin "37") (pinfunction "GPIO13/AVD33_USB_37") (pintype "passive"))
      (node (ref "U5") (pin "5") (pinfunction "AVD33_LD_5") (pintype "passive"))
    )
    (net (code "17") (name "/DVDD_1.85") (class "Default")
      (node (ref "C22") (pin "2") (pinfunction "2_2") (pintype "passive"))
      (node (ref "C23") (pin "2") (pinfunction "2_2") (pintype "passive"))
      (node (ref "C24") (pin "2") (pinfunction "2_2") (pintype "passive"))
      (node (ref "C25") (pin "2") (pinfunction "2_2") (pintype "passive"))
      (node (ref "FB2") (pin "1") (pinfunction "1_1") (pintype "passive"))
      (node (ref "U5") (pin "26") (pinfunction "DVDD18_26") (pintype "passive"))
      (node (ref "U5") (pin "35") (pinfunction "DVDD18_35") (pintype "passive"))
      (node (ref "U5") (pin "53") (pinfunction "DVDD18_53") (pintype "passive"))
      (node (ref "U5") (pin "56") (pinfunction "LDO18_56") (pintype "passive"))
    )
    (net (code "18") (name "/D_N") (class "Default")
      (node (ref "D4") (pin "2") (pinfunction "D-_2") (pintype "passive"))
      (node (ref "J6") (pin "A7") (pinfunction "Dn1_A7") (pintype "passive"))
      (node (ref "J6") (pin "B7") (pinfunction "Dn2_B7") (pintype "passive"))
      (node (ref "U5") (pin "38") (pinfunction "GPIO12_USB_DN_38") (pintype "passive"))
    )
    (net (code "19") (name "/D_P") (class "Default")
      (node (ref "D4") (pin "1") (pinfunction "D+_1") (pintype "passive"))
      (node (ref "J6") (pin "A6") (pinfunction "Dp1_A6") (pintype "passive"))
      (node (ref "J6") (pin "B6") (pinfunction "Dp2_B6") (pintype "passive"))
      (node (ref "U5") (pin "39") (pinfunction "GPIO12_USB_DP_39") (pintype "passive"))
    )
    (net (code "20") (name "/GPS_PPS_OUT") (class "Default")
      (node (ref "IC1") (pin "3") (pinfunction "TIMEPULSE_3") (pintype "passive"))
      (node (ref "IC2") (pin "4") (pinfunction "TIMEPULSE_4") (pintype "passive"))
      (node (ref "J3") (pin "5") (pinfunction "5_5") (pintype "passive"))
      (node (ref "U4") (pin "3") (pinfunction "B1_3") (pintype "passive"))
    )
    (net (code "21") (name "/LED0") (class "Default")
      (node (ref "J4") (pin "12") (pinfunction "K_GREEN_12") (pintype "passive"))
      (node (ref "R31") (pin "2") (pinfunction "2_2") (pintype "passive"))
      (node (ref "U5") (pin "27") (pinfunction "GPIO5(LED0)_27") (pintype "passive"))
    )
    (net (code "22") (name "/LED1") (class "Default")
      (node (ref "J4") (pin "14") (pinfunction "K_YELLOW_14") (pintype "passive"))
      (node (ref "R32") (pin "2") (pinfunction "2_2") (pintype "passive"))
      (node (ref "U5") (pin "28") (pinfunction "GPIO4(LED1)_28") (pintype "passive"))
    )
    (net (code "23") (name "/LNA_EN") (class "Default")
      (node (ref "IC1") (pin "14") (pinfunction "LNA_EN_14") (pintype "passive"))
      (node (ref "IC2") (pin "13") (pinfunction "LNA_EN_13") (pintype "passive"))
      (node (ref "R14") (pin "1") (pinfunction "1_1") (pintype "passive"))
    )
    (net (code "24") (name "/MDI0_N") (class "Default")
      (node (ref "J4") (pin "2") (pinfunction "TD1-_2") (pintype "passive"))
      (node (ref "U5") (pin "4") (pinfunction "TXVN_A_4") (pintype "passive"))
    )
    (net (code "25") (name "/MDI0_P") (class "Default")
      (node (ref "J4") (pin "1") (pinfunction "TD1+_1") (pintype "passive"))
      (node (ref "U5") (pin "3") (pinfunction "TXVP_A_3") (pintype "passive"))
    )
    (net (code "26") (name "/MDI1_N") (class "Default")
      (node (ref "J4") (pin "4") (pinfunction "TD2-_4") (pintype "passive"))
      (node (ref "U5") (pin "7") (pinfunction "TXVP_B_7") (pintype "passive"))
    )
    (net (code "27") (name "/MDI1_P") (class "Default")
      (node (ref "J4") (pin "3") (pinfunction "TD2+_3") (pintype "passive"))
      (node (ref "U5") (pin "6") (pinfunction "TXVP_B_6") (pintype "passive"))
    )
    (net (code "28") (name "/MDI2_N") (class "Default")
      (node (ref "J4") (pin "6") (pinfunction "TD3-_6") (pintype "passive"))
      (node (ref "U5") (pin "11") (pinfunction "TXVN_C_11") (pintype "passive"))
    )
    (net (code "29") (name "/MDI2_P") (class "Default")
      (node (ref "J4") (pin "5") (pinfunction "TD3+_5") (pintype "passive"))
      (node (ref "U5") (pin "10") (pinfunction "TXVP_C_10") (pintype "passive"))
    )
    (net (code "30") (name "/MDI3_N") (class "Default")
      (node (ref "J4") (pin "8") (pinfunction "TD4-_8") (pintype "passive"))
      (node (ref "U5") (pin "14") (pinfunction "TXVN_D_14") (pintype "passive"))
    )
    (net (code "31") (name "/MDI3_P") (class "Default")
      (node (ref "J4") (pin "7") (pinfunction "TD4+_7") (pintype "passive"))
      (node (ref "U5") (pin "13") (pinfunction "TXVP_D_13") (pintype "passive"))
    )
    (net (code "32") (name "/MUX1_CTRL") (class "Default")
      (node (ref "R6") (pin "1") (pinfunction "1_1") (pintype "passive"))
      (node (ref "S1") (pin "3") (pinfunction "COM_1_3") (pintype "passive"))
      (node (ref "U2") (pin "6") (pinfunction "S_6") (pintype "passive"))
    )
    (net (code "33") (name "/MUX2_CTRL") (class "Default")
      (node (ref "R7") (pin "1") (pinfunction "1_1") (pintype "passive"))
      (node (ref "S1") (pin "4") (pinfunction "COM_2_4") (pintype "passive"))
      (node (ref "U4") (pin "6") (pinfunction "S_6") (pintype "passive"))
    )
    (net (code "34") (name "/RESET_N") (class "Default")
      (node (ref "R19") (pin "1") (pinfunction "1_1") (pintype "passive"))
      (node (ref "U5") (pin "23") (pinfunction "HW_RSTN_23") (pintype "passive"))
    )
    (net (code "35") (name "/RF") (class "Default")
      (node (ref "C7") (pin "2") (pinfunction "2_2") (pintype "passive"))
      (node (ref "IC1") (pin "11") (pinfunction "RF_IN_11") (pintype "passive"))
      (node (ref "IC2") (pin "11") (pinfunction "RF_IN_11") (pintype "passive"))
    )
    (net (code "36") (name "/SPI_CLK") (class "Default")
      (node (ref "R35") (pin "2") (pinfunction "2_2") (pintype "passive"))
      (node (ref "U5") (pin "51") (pinfunction "SPI_CLK_51") (pintype "passive"))
      (node (ref "U7") (pin "6") (pinfunction "SCK_6") (pintype "input"))
    )
    (net (code "37") (name "/SPI_CS") (class "Default")
      (node (ref "R36") (pin "2") (pinfunction "2_2") (pintype "passive"))
      (node (ref "U5") (pin "50") (pinfunction "SPI_CS0_50") (pintype "passive"))
      (node (ref "U7") (pin "1") (pinfunction "~{CE}_1") (pintype "input"))
    )
    (net (code "38") (name "/SPI_DIO") (class "Default")
      (node (ref "R34") (pin "2") (pinfunction "2_2") (pintype "passive"))
      (node (ref "R39") (pin "2") (pinfunction "2_2") (pintype "passive"))
      (node (ref "U5") (pin "52") (pinfunction "SPI_DIO_52") (pintype "passive"))
      (node (ref "U7") (pin "5") (pinfunction "SI_5") (pintype "input"))
    )
    (net (code "39") (name "/SSRX_N") (class "Default")
      (node (ref "D5") (pin "2") (pinfunction "D-_2") (pintype "passive"))
      (node (ref "J6") (pin "A10") (pinfunction "SSRXn2_A10") (pintype "passive"))
      (node (ref "J6") (pin "B10") (pinfunction "SSRXn1_B10") (pintype "passive"))
      (node (ref "U5") (pin "44") (pinfunction "SSUSBRXN_44") (pintype "passive"))
    )
    (net (code "40") (name "/SSRX_P") (class "Default")
      (node (ref "D5") (pin "1") (pinfunction "D+_1") (pintype "passive"))
      (node (ref "J6") (pin "A11") (pinfunction "SSRXp2_A11") (pintype "passive"))
      (node (ref "J6") (pin "B11") (pinfunction "SSRXp1_B11") (pintype "passive"))
      (node (ref "U5") (pin "45") (pinfunction "SSUSBRXP_45") (pintype "passive"))
    )
    (net (code "41") (name "/SSTX_N") (class "Default")
      (node (ref "C9") (pin "2") (pinfunction "2_2") (pintype "passive"))
      (node (ref "D3") (pin "2") (pinfunction "D-_2") (pintype "passive"))
      (node (ref "U5") (pin "41") (pinfunction "SSUSB_TXN_41") (pintype "passive"))
    )
    (net (code "42") (name "/SSTX_P") (class "Default")
      (node (ref "C8") (pin "2") (pinfunction "2_2") (pintype "passive"))
      (node (ref "D3") (pin "1") (pinfunction "D+_1") (pintype "passive"))
      (node (ref "U5") (pin "42") (pinfunction "SSUSB_TXP_42") (pintype "passive"))
    )
    (net (code "43") (name "/USB3.0_SSTX_N") (class "Default")
      (node (ref "C9") (pin "1") (pinfunction "1_1") (pintype "passive"))
      (node (ref "J6") (pin "A3") (pinfunction "SSTXn1_A3") (pintype "passive"))
      (node (ref "J6") (pin "B3") (pinfunction "SSTXn2_B3") (pintype "passive"))
    )
    (net (code "44") (name "/USB3.0_SSTX_P") (class "Default")
      (node (ref "C8") (pin "1") (pinfunction "1_1") (pintype "passive"))
      (node (ref "J6") (pin "A2") (pinfunction "SSTXp1_A2") (pintype "passive"))
      (node (ref "J6") (pin "B2") (pinfunction "SSTXp2_B2") (pintype "passive"))
    )
    (net (code "45") (name "/VBUS") (class "Default")
      (node (ref "R17") (pin "1") (pinfunction "1_1") (pintype "passive"))
      (node (ref "R18") (pin "2") (pinfunction "2_2") (pintype "passive"))
      (node (ref "U5") (pin "34") (pinfunction "GPIO9(VBUS)_34") (pintype "passive"))
    )
    (net (code "46") (name "/VCORE_LDO") (class "Default")
      (node (ref "C21") (pin "2") (pinfunction "2_2") (pintype "passive"))
      (node (ref "FB1") (pin "1") (pinfunction "1_1") (pintype "passive"))
      (node (ref "U5") (pin "55") (pinfunction "VCORE_LDO_55") (pintype "passive"))
    )
    (net (code "47") (name "/XTL20N") (class "Default")
      (node (ref "R27") (pin "2") (pinfunction "2_2") (pintype "passive"))
      (node (ref "U5") (pin "16") (pinfunction "XTAL_XO_16") (pintype "passive"))
    )
    (net (code "48") (name "/XTL20P") (class "Default")
      (node (ref "R26") (pin "2") (pinfunction "2_2") (pintype "passive"))
      (node (ref "U5") (pin "17") (pinfunction "XTAL_IN_17") (pintype "passive"))
    )
    (net (code "49") (name "CHASSIS_GND") (class "Default")
      (node (ref "C6") (pin "1") (pinfunction "1_1") (pintype "passive"))
      (node (ref "J4") (pin "15") (pinfunction "MH1_15") (pintype "passive"))
      (node (ref "J4") (pin "16") (pinfunction "MH2_16") (pintype "passive"))
      (node (ref "R15") (pin "1") (pinfunction "1_1") (pintype "passive"))
    )
    (net (code "50") (name "DVDD_33") (class "Default")
      (node (ref "C18") (pin "2") (pinfunction "2_2") (pintype "passive"))
      (node (ref "C20") (pin "2") (pinfunction "2_2") (pintype "passive"))
      (node (ref "C31") (pin "2") (pinfunction "2_2") (pintype "passive"))
      (node (ref "C32") (pin "2") (pinfunction "2_2") (pintype "passive"))
      (node (ref "C33") (pin "2") (pinfunction "2_2") (pintype "passive"))
      (node (ref "C34") (pin "2") (pinfunction "2_2") (pintype "passive"))
      (node (ref "FB4") (pin "1") (pinfunction "1_1") (pintype "passive"))
      (node (ref "FB5") (pin "1") (pinfunction "1_1") (pintype "passive"))
      (node (ref "L2") (pin "2") (pinfunction "2_2") (pintype "passive"))
      (node (ref "R10") (pin "2") (pinfunction "2_2") (pintype "passive"))
      (node (ref "R19") (pin "2") (pinfunction "2_2") (pintype "passive"))
      (node (ref "R22") (pin "2") (pinfunction "2_2") (pintype "passive"))
      (node (ref "R24") (pin "2") (pinfunction "2_2") (pintype "passive"))
      (node (ref "R25") (pin "2") (pinfunction "2_2") (pintype "passive"))
      (node (ref "R31") (pin "1") (pinfunction "1_1") (pintype "passive"))
      (node (ref "R32") (pin "1") (pinfunction "1_1") (pintype "passive"))
      (node (ref "R34") (pin "1") (pinfunction "1_1") (pintype "passive"))
      (node (ref "R35") (pin "1") (pinfunction "1_1") (pintype "passive"))
      (node (ref "R36") (pin "1") (pinfunction "1_1") (pintype "passive"))
      (node (ref "R37") (pin "1") (pinfunction "1_1") (pintype "passive"))
      (node (ref "R38") (pin "1") (pinfunction "1_1") (pintype "passive"))
      (node (ref "R8") (pin "2") (pinfunction "2_2") (pintype "passive"))
      (node (ref "U5") (pin "25") (pinfunction "DVDD33_25") (pintype "passive"))
      (node (ref "U5") (pin "36") (pinfunction "DVDD33_36") (pintype "passive"))
      (node (ref "U5") (pin "54") (pinfunction "AVDD33_LDO_54") (pintype "passive"))
      (node (ref "U5") (pin "59") (pinfunction "AVD33_BUCK_59") (pintype "passive"))
      (node (ref "U6") (pin "1") (pinfunction "VO/VFB_1") (pintype "bidirectional"))
      (node (ref "U7") (pin "8") (pinfunction "VDD_8") (pintype "power_in"))
    )
    (net (code "51") (name "GND") (class "Default")
      (node (ref "C1") (pin "1") (pinfunction "1_1") (pintype "passive"))
      (node (ref "C10") (pin "1") (pinfunction "1_1") (pintype "passive"))
      (node (ref "C11") (pin "1") (pinfunction "1_1") (pintype "passive"))
      (node (ref "C12") (pin "1") (pinfunction "1_1") (pintype "passive"))
      (node (ref "C13") (pin "1") (pinfunction "1_1") (pintype "passive"))
      (node (ref "C14") (pin "1") (pinfunction "1_1") (pintype "passive"))
      (node (ref "C15") (pin "1") (pinfunction "1_1") (pintype "passive"))
      (node (ref "C16") (pin "1") (pinfunction "1_1") (pintype "passive"))
      (node (ref "C17") (pin "1") (pinfunction "1_1") (pintype "passive"))
      (node (ref "C18") (pin "1") (pinfunction "1_1") (pintype "passive"))
      (node (ref "C19") (pin "1") (pinfunction "1_1") (pintype "passive"))
      (node (ref "C2") (pin "1") (pinfunction "1_1") (pintype "passive"))
      (node (ref "C20") (pin "1") (pinfunction "1_1") (pintype "passive"))
      (node (ref "C21") (pin "1") (pinfunction "1_1") (pintype "passive"))
      (node (ref "C22") (pin "1") (pinfunction "1_1") (pintype "passive"))
      (node (ref "C23") (pin "1") (pinfunction "1_1") (pintype "passive"))
      (node (ref "C24") (pin "1") (pinfunction "1_1") (pintype "passive"))
      (node (ref "C25") (pin "1") (pinfunction "1_1") (pintype "passive"))
      (node (ref "C26") (pin "1") (pinfunction "1_1") (pintype "passive"))
      (node (ref "C27") (pin "1") (pinfunction "1_1") (pintype "passive"))
      (node (ref "C28") (pin "1") (pinfunction "1_1") (pintype "passive"))
      (node (ref "C29") (pin "1") (pinfunction "1_1") (pintype "passive"))
      (node (ref "C3") (pin "1") (pinfunction "1_1") (pintype "passive"))
      (node (ref "C30") (pin "1") (pinfunction "1_1") (pintype "passive"))
      (node (ref "C31") (pin "1") (pinfunction "1_1") (pintype "passive"))
      (node (ref "C32") (pin "1") (pinfunction "1_1") (pintype "passive"))
      (node (ref "C33") (pin "1") (pinfunction "1_1") (pintype "passive"))
      (node (ref "C34") (pin "1") (pinfunction "1_1") (pintype "passive"))
      (node (ref "C35") (pin "1") (pinfunction "1_1") (pintype "passive"))
      (node (ref "C36") (pin "1") (pinfunction "1_1") (pintype "passive"))
      (node (ref "C37") (pin "1") (pinfunction "1_1") (pintype "passive"))
      (node (ref "C38") (pin "1") (pinfunction "1_1") (pintype "passive"))
      (node (ref "C39") (pin "1") (pinfunction "1_1") (pintype "passive"))
      (node (ref "C4") (pin "1") (pinfunction "1_1") (pintype "passive"))
      (node (ref "C40") (pin "1") (pinfunction "1_1") (pintype "passive"))
      (node (ref "C41") (pin "1") (pinfunction "1_1") (pintype "passive"))
      (node (ref "C42") (pin "1") (pinfunction "1_1") (pintype "passive"))
      (node (ref "C43") (pin "1") (pinfunction "1_1") (pintype "passive"))
      (node (ref "C44") (pin "1") (pinfunction "1_1") (pintype "passive"))
      (node (ref "C5") (pin "1") (pinfunction "1_1") (pintype "passive"))
      (node (ref "C6") (pin "2") (pinfunction "2_2") (pintype "passive"))
      (node (ref "D3") (pin "3") (pinfunction "GND_3") (pintype "passive"))
      (node (ref "D4") (pin "3") (pinfunction "GND_3") (pintype "passive"))
      (node (ref "D5") (pin "3") (pinfunction "GND_3") (pintype "passive"))
      (node (ref "IC1") (pin "10") (pinfunction "GND_1_10") (pintype "passive"))
      (node (ref "IC1") (pin "12") (pinfunction "GND_2_12") (pintype "passive"))
      (node (ref "IC1") (pin "13") (pinfunction "GND_3_13") (pintype "passive"))
      (node (ref "IC1") (pin "24") (pinfunction "GND_4_24") (pintype "passive"))
      (node (ref "IC1") (pin "7") (pinfunction "V_USB_7") (pintype "passive"))
      (node (ref "IC2") (pin "1") (pinfunction "GND_1_1") (pintype "passive"))
      (node (ref "IC2") (pin "10") (pinfunction "GND_2_10") (pintype "passive"))
      (node (ref "IC2") (pin "12") (pinfunction "GND_3_12") (pintype "passive"))
      (node (ref "J1") (pin "2") (pinfunction "2_2") (pintype "passive"))
      (node (ref "J1") (pin "3") (pinfunction "3_3") (pintype "passive"))
      (node (ref "J1") (pin "4") (pinfunction "4_4") (pintype "passive"))
      (node (ref "J1") (pin "5") (pinfunction "5_5") (pintype "passive"))
      (node (ref "J2") (pin "2") (pinfunction "2_2") (pintype "passive"))
      (node (ref "J2") (pin "3") (pinfunction "3_3") (pintype "passive"))
      (node (ref "J2") (pin "4") (pinfunction "4_4") (pintype "passive"))
      (node (ref "J2") (pin "5") (pinfunction "5_5") (pintype "passive"))
      (node (ref "J3") (pin "1") (pinfunction "1_1") (pintype "passive"))
      (node (ref "J4") (pin "10") (pinfunction "GND_10") (pintype "passive"))
      (node (ref "J5") (pin "2") (pinfunction "2_2") (pintype "passive"))
      (node (ref "J5") (pin "3") (pinfunction "3_3") (pintype "passive"))
      (node (ref "J5") (pin "4") (pinfunction "4_4") (pintype "passive"))
      (node (ref "J5") (pin "5") (pinfunction "5_5") (pintype "passive"))
      (node (ref "J6") (pin "A1") (pinfunction "GND_A1") (pintype "passive"))
      (node (ref "J6") (pin "A12") (pinfunction "GND_A12") (pintype "passive"))
      (node (ref "J6") (pin "B1") (pinfunction "GND_B1") (pintype "passive"))
      (node (ref "J6") (pin "B12") (pinfunction "GND_B12") (pintype "passive"))
      (node (ref "R1") (pin "2") (pinfunction "2_2") (pintype "passive"))
      (node (ref "R15") (pin "2") (pinfunction "2_2") (pintype "passive"))
      (node (ref "R16") (pin "2") (pinfunction "2_2") (pintype "passive"))
      (node (ref "R18") (pin "1") (pinfunction "1_1") (pintype "passive"))
      (node (ref "R21") (pin "1") (pinfunction "1_1") (pintype "passive"))
      (node (ref "R29") (pin "2") (pinfunction "2_2") (pintype "passive"))
      (node (ref "R30") (pin "2") (pinfunction "2_2") (pintype "passive"))
      (node (ref "R33") (pin "1") (pinfunction "1_1") (pintype "passive"))
      (node (ref "R4") (pin "1") (pinfunction "1_1") (pintype "passive"))
      (node (ref "R41") (pin "2") (pinfunction "2_2") (pintype "passive"))
      (node (ref "S1") (pin "1") (pinfunction "NO_1_1") (pintype "passive"))
      (node (ref "S1") (pin "2") (pinfunction "NO_2_2") (pintype "passive"))
      (node (ref "U1") (pin "4") (pinfunction "GND_4") (pintype "passive"))
      (node (ref "U2") (pin "2") (pinfunction "GND_2") (pintype "passive"))
      (node (ref "U3") (pin "4") (pinfunction "GND_4") (pintype "passive"))
      (node (ref "U4") (pin "2") (pinfunction "GND_2") (pintype "passive"))
      (node (ref "U5") (pin "1") (pinfunction "AVSS33_BUCK_1") (pintype "passive"))
      (node (ref "U5") (pin "2") (pinfunction "AVSS33_BUCK_2") (pintype "passive"))
      (node (ref "U5") (pin "61") (pinfunction "E_PAD_61") (pintype "passive"))
      (node (ref "U6") (pin "2") (pinfunction "GND_2") (pintype "power_in"))
      (node (ref "U6") (pin "7") (pinfunction "Thermal_Pad_7") (pintype "power_in"))
      (node (ref "U7") (pin "4") (pinfunction "VSS_4") (pintype "power_in"))
      (node (ref "U7") (pin "9") (pinfunction "VSS_9") (pintype "power_in"))
      (node (ref "U8") (pin "2") (pinfunction "GND_2") (pintype "power_in"))
      (node (ref "U8") (pin "7") (pinfunction "Thermal_Pad_7") (pintype "power_in"))
      (node (ref "Y1") (pin "2") (pinfunction "GND_2") (pintype "passive"))
      (node (ref "Y1") (pin "4") (pinfunction "GND_4") (pintype "passive"))
    )
    (net (code "52") (name "Net-(C5-Pad2)") (class "Default")
      (node (ref "C5") (pin "2") (pinfunction "2_2") (pintype "passive"))
      (node (ref "L1") (pin "1") (pinfunction "1_1") (pintype "passive"))
      (node (ref "R12") (pin "2") (pinfunction "2_2") (pintype "passive"))
    )
    (net (code "53") (name "Net-(C13-Pad2)") (class "Default")
      (node (ref "C13") (pin "2") (pinfunction "2_2") (pintype "passive"))
      (node (ref "R26") (pin "1") (pinfunction "1_1") (pintype "passive"))
      (node (ref "Y1") (pin "1") (pinfunction "1_1") (pintype "passive"))
    )
    (net (code "54") (name "Net-(C14-Pad2)") (class "Default")
      (node (ref "C14") (pin "2") (pinfunction "2_2") (pintype "passive"))
      (node (ref "R27") (pin "1") (pinfunction "1_1") (pintype "passive"))
      (node (ref "Y1") (pin "3") (pinfunction "3_3") (pintype "passive"))
    )
    (net (code "55") (name "Net-(D1-PadA)") (class "Default")
      (node (ref "D1") (pin "A") (pinfunction "A_A") (pintype "passive"))
      (node (ref "R2") (pin "1") (pinfunction "1_1") (pintype "passive"))
    )
    (net (code "56") (name "Net-(D2-PadA)") (class "Default")
      (node (ref "D2") (pin "A") (pinfunction "A_A") (pintype "passive"))
      (node (ref "R5") (pin "1") (pinfunction "1_1") (pintype "passive"))
    )
    (net (code "57") (name "Net-(J4-A_GREEN)") (class "Default")
      (node (ref "J4") (pin "11") (pinfunction "A_GREEN_11") (pintype "passive"))
      (node (ref "R8") (pin "1") (pinfunction "1_1") (pintype "passive"))
    )
    (net (code "58") (name "Net-(J4-A_YELLOW)") (class "Default")
      (node (ref "J4") (pin "13") (pinfunction "A_YELLOW_13") (pintype "passive"))
      (node (ref "R10") (pin "1") (pinfunction "1_1") (pintype "passive"))
    )
    (net (code "59") (name "Net-(J6-CC1)") (class "Default")
      (node (ref "J6") (pin "A5") (pinfunction "CC1_A5") (pintype "passive"))
      (node (ref "R29") (pin "1") (pinfunction "1_1") (pintype "passive"))
    )
    (net (code "60") (name "Net-(J6-CC2)") (class "Default")
      (node (ref "J6") (pin "B5") (pinfunction "CC2_B5") (pintype "passive"))
      (node (ref "R30") (pin "1") (pinfunction "1_1") (pintype "passive"))
    )
    (net (code "61") (name "Net-(J6-Shield)") (class "Default")
      (node (ref "C15") (pin "2") (pinfunction "2_2") (pintype "passive"))
      (node (ref "J6") (pin "S") (pinfunction "Shield_S") (pintype "passive"))
      (node (ref "R33") (pin "2") (pinfunction "2_2") (pintype "passive"))
    )
    (net (code "62") (name "Net-(Q1-G)") (class "Default")
      (node (ref "Q1") (pin "1") (pinfunction "G_1") (pintype "passive"))
      (node (ref "R13") (pin "1") (pinfunction "1_1") (pintype "passive"))
      (node (ref "R14") (pin "2") (pinfunction "2_2") (pintype "passive"))
      (node (ref "R16") (pin "1") (pinfunction "1_1") (pintype "passive"))
    )
    (net (code "63") (name "Net-(Q1-S)") (class "Default")
      (node (ref "Q1") (pin "2") (pinfunction "S_2") (pintype "passive"))
      (node (ref "R12") (pin "1") (pinfunction "1_1") (pintype "passive"))
    )
    (net (code "64") (name "Net-(U1-~{OE1})") (class "Default")
      (node (ref "R1") (pin "1") (pinfunction "1_1") (pintype "passive"))
      (node (ref "U1") (pin "1") (pinfunction "~{OE1}_1") (pintype "passive"))
      (node (ref "U1") (pin "7") (pinfunction "~{OE2}_7") (pintype "passive"))
    )
    (net (code "65") (name "Net-(U3-~{OE1})") (class "Default")
      (node (ref "R4") (pin "2") (pinfunction "2_2") (pintype "passive"))
      (node (ref "U3") (pin "1") (pinfunction "~{OE1}_1") (pintype "passive"))
      (node (ref "U3") (pin "7") (pinfunction "~{OE2}_7") (pintype "passive"))
    )
    (net (code "66") (name "Net-(U4-B2)") (class "Default")
      (node (ref "J2") (pin "1") (pinfunction "1_1") (pintype "passive"))
      (node (ref "U4") (pin "1") (pinfunction "B2_1") (pintype "passive"))
    )
    (net (code "67") (name "Net-(U5-AVDD18_XTAL)") (class "Default")
      (node (ref "C28") (pin "2") (pinfunction "2_2") (pintype "passive"))
      (node (ref "C29") (pin "2") (pinfunction "2_2") (pintype "passive"))
      (node (ref "FB3") (pin "1") (pinfunction "1_1") (pintype "passive"))
      (node (ref "U5") (pin "15") (pinfunction "AVDD18_XTAL_15") (pintype "passive"))
    )
    (net (code "68") (name "Net-(U5-GPIO3(LED2))") (class "Default")
      (node (ref "R22") (pin "1") (pinfunction "1_1") (pintype "passive"))
      (node (ref "U5") (pin "29") (pinfunction "GPIO3(LED2)_29") (pintype "passive"))
    )
    (net (code "69") (name "Net-(U5-GPIO8(WAKEUP_B))") (class "Default")
      (node (ref "R25") (pin "1") (pinfunction "1_1") (pintype "passive"))
      (node (ref "U5") (pin "33") (pinfunction "GPIO8(WAKEUP_B)_33") (pintype "passive"))
    )
    (net (code "70") (name "Net-(U5-GPIO10(SYNCE_LOCK))") (class "Default")
      (node (ref "R24") (pin "1") (pinfunction "1_1") (pintype "passive"))
      (node (ref "U5") (pin "19") (pinfunction "GPIO10(SYNCE_LOCK)_19") (pintype "passive"))
    )
    (net (code "71") (name "Net-(U5-MPXP)") (class "Default")
      (node (ref "R21") (pin "2") (pinfunction "2_2") (pintype "passive"))
      (node (ref "U5") (pin "9") (pinfunction "MPXP_9") (pintype "passive"))
    )
    (net (code "72") (name "Net-(U6-SW)") (class "Default")
      (node (ref "L2") (pin "1") (pinfunction "1_1") (pintype "passive"))
      (node (ref "U6") (pin "3") (pinfunction "SW_3") (pintype "passive"))
    )
    (net (code "73") (name "Net-(U7-SO)") (class "Default")
      (node (ref "R39") (pin "1") (pinfunction "1_1") (pintype "passive"))
      (node (ref "U7") (pin "2") (pinfunction "SO_2") (pintype "output"))
    )
    (net (code "74") (name "Net-(U7-~{HOLD})") (class "Default")
      (node (ref "R37") (pin "2") (pinfunction "2_2") (pintype "passive"))
      (node (ref "U7") (pin "7") (pinfunction "~{HOLD}_7") (pintype "input"))
    )
    (net (code "75") (name "Net-(U7-~{WP})") (class "Default")
      (node (ref "R38") (pin "2") (pinfunction "2_2") (pintype "passive"))
      (node (ref "U7") (pin "3") (pinfunction "~{WP}_3") (pintype "input"))
    )
    (net (code "76") (name "Net-(U8-SW)") (class "Default")
      (node (ref "L3") (pin "1") (pinfunction "1_1") (pintype "passive"))
      (node (ref "U8") (pin "3") (pinfunction "SW_3") (pintype "passive"))
    )
    (net (code "77") (name "Net-(U8-VO{slash}VFB)") (class "Default")
      (node (ref "R40") (pin "2") (pinfunction "2_2") (pintype "passive"))
      (node (ref "R41") (pin "1") (pinfunction "1_1") (pintype "passive"))
      (node (ref "U8") (pin "1") (pinfunction "VO/VFB_1") (pintype "bidirectional"))
    )
    (net (code "78") (name "VBUS_+5V") (class "Default")
      (node (ref "C1") (pin "2") (pinfunction "2_2") (pintype "passive"))
      (node (ref "C19") (pin "2") (pinfunction "2_2") (pintype "passive"))
      (node (ref "C2") (pin "2") (pinfunction "2_2") (pintype "passive"))
      (node (ref "C3") (pin "2") (pinfunction "2_2") (pintype "passive"))
      (node (ref "C4") (pin "2") (pinfunction "2_2") (pintype "passive"))
      (node (ref "C40") (pin "2") (pinfunction "2_2") (pintype "passive"))
      (node (ref "J3") (pin "2") (pinfunction "2_2") (pintype "passive"))
      (node (ref "J6") (pin "A4") (pinfunction "VBUS_A4") (pintype "passive"))
      (node (ref "J6") (pin "A9") (pinfunction "VBUS_A9") (pintype "passive"))
      (node (ref "J6") (pin "B4") (pinfunction "VBUS_B4") (pintype "passive"))
      (node (ref "J6") (pin "B9") (pinfunction "VBUS_B9") (pintype "passive"))
      (node (ref "R11") (pin "2") (pinfunction "2_2") (pintype "passive"))
      (node (ref "R17") (pin "2") (pinfunction "2_2") (pintype "passive"))
      (node (ref "R2") (pin "2") (pinfunction "2_2") (pintype "passive"))
      (node (ref "R5") (pin "2") (pinfunction "2_2") (pintype "passive"))
      (node (ref "R6") (pin "2") (pinfunction "2_2") (pintype "passive"))
      (node (ref "R7") (pin "2") (pinfunction "2_2") (pintype "passive"))
      (node (ref "U1") (pin "8") (pinfunction "VCC_8") (pintype "passive"))
      (node (ref "U2") (pin "5") (pinfunction "VCC_5") (pintype "passive"))
      (node (ref "U3") (pin "8") (pinfunction "VCC_8") (pintype "passive"))
      (node (ref "U4") (pin "5") (pinfunction "VCC_5") (pintype "passive"))
      (node (ref "U6") (pin "4") (pinfunction "VIN_SW_4") (pintype "input"))
      (node (ref "U6") (pin "5") (pinfunction "VIN_A_5") (pintype "input"))
      (node (ref "U6") (pin "6") (pinfunction "VINH_6") (pintype "input"))
      (node (ref "U8") (pin "4") (pinfunction "VIN_SW_4") (pintype "input"))
      (node (ref "U8") (pin "5") (pinfunction "VIN_A_5") (pintype "input"))
      (node (ref "U8") (pin "6") (pinfunction "VINH_6") (pintype "input"))
    )
    (net (code "79") (name "VCCK10") (class "Default")
      (node (ref "C30") (pin "2") (pinfunction "2_2") (pintype "passive"))
      (node (ref "C41") (pin "2") (pinfunction "2_2") (pintype "passive"))
      (node (ref "C42") (pin "2") (pinfunction "2_2") (pintype "passive"))
      (node (ref "C43") (pin "2") (pinfunction "2_2") (pintype "passive"))
      (node (ref "C44") (pin "2") (pinfunction "2_2") (pintype "passive"))
      (node (ref "L3") (pin "2") (pinfunction "2_2") (pintype "passive"))
      (node (ref "R40") (pin "1") (pinfunction "1_1") (pintype "passive"))
      (node (ref "U5") (pin "24") (pinfunction "VCCK_24") (pintype "passive"))
      (node (ref "U5") (pin "30") (pinfunction "VCCK_30") (pintype "passive"))
      (node (ref "U5") (pin "31") (pinfunction "VCCK_31") (pintype "passive"))
      (node (ref "U5") (pin "32") (pinfunction "VCCK_32") (pintype "passive"))
      (node (ref "U5") (pin "57") (pinfunction "VCCK_57") (pintype "passive"))
      (node (ref "U5") (pin "58") (pinfunction "VCCK_58") (pintype "passive"))
    )
    (net (code "80") (name "VDD_NEO") (class "Default")
      (node (ref "C10") (pin "2") (pinfunction "2_2") (pintype "passive"))
      (node (ref "C11") (pin "2") (pinfunction "2_2") (pintype "passive"))
      (node (ref "C12") (pin "2") (pinfunction "2_2") (pintype "passive"))
      (node (ref "FB5") (pin "2") (pinfunction "2_2") (pintype "passive"))
      (node (ref "IC1") (pin "2") (pinfunction "D_SEL_2") (pintype "passive"))
      (node (ref "IC1") (pin "22") (pinfunction "V_BCKP_22") (pintype "passive"))
      (node (ref "IC1") (pin "23") (pinfunction "VCC_23") (pintype "passive"))
      (node (ref "IC2") (pin "6") (pinfunction "V_BCKP_6") (pintype "passive"))
      (node (ref "IC2") (pin "8") (pinfunction "VCC_8") (pintype "passive"))
    )
    (net (code "81") (name "unconnected-(IC1-EXTINT-Pad4)") (class "Default")
      (node (ref "IC1") (pin "4") (pinfunction "EXTINT_4") (pintype "passive+no_connect"))
    )
    (net (code "82") (name "unconnected-(IC1-RESERVED_1-Pad15)") (class "Default")
      (node (ref "IC1") (pin "15") (pinfunction "RESERVED_1_15") (pintype "passive+no_connect"))
    )
    (net (code "83") (name "unconnected-(IC1-RESERVED_2-Pad16)") (class "Default")
      (node (ref "IC1") (pin "16") (pinfunction "RESERVED_2_16") (pintype "passive+no_connect"))
    )
    (net (code "84") (name "unconnected-(IC1-RESERVED_3-Pad17)") (class "Default")
      (node (ref "IC1") (pin "17") (pinfunction "RESERVED_3_17") (pintype "passive+no_connect"))
    )
    (net (code "85") (name "unconnected-(IC1-RESET_N-Pad8)") (class "Default")
      (node (ref "IC1") (pin "8") (pinfunction "RESET_N_8") (pintype "passive+no_connect"))
    )
    (net (code "86") (name "unconnected-(IC1-SAFEBOOT_N-Pad1)") (class "Default")
      (node (ref "IC1") (pin "1") (pinfunction "SAFEBOOT_N_1") (pintype "passive+no_connect"))
    )
    (net (code "87") (name "unconnected-(IC1-SCL_{slash}_SPI_SLK_-Pad19)") (class "Default")
      (node (ref "IC1") (pin "19") (pinfunction "SCL_/_SPI_SLK__19") (pintype "passive"))
    )
    (net (code "88") (name "unconnected-(IC1-SDA_{slash}_SPI_CS_N-Pad18)") (class "Default")
      (node (ref "IC1") (pin "18") (pinfunction "SDA_/_SPI_CS_N_18") (pintype "passive"))
    )
    (net (code "89") (name "unconnected-(IC1-USB_DM-Pad5)") (class "Default")
      (node (ref "IC1") (pin "5") (pinfunction "USB_DM_5") (pintype "passive+no_connect"))
    )
    (net (code "90") (name "unconnected-(IC1-USB_DP-Pad6)") (class "Default")
      (node (ref "IC1") (pin "6") (pinfunction "USB_DP_6") (pintype "passive+no_connect"))
    )
    (net (code "91") (name "unconnected-(IC1-VCC_RF-Pad9)") (class "Default")
      (node (ref "IC1") (pin "9") (pinfunction "VCC_RF_9") (pintype "passive+no_connect"))
    )
    (net (code "92") (name "unconnected-(IC2-EXTINT-Pad5)") (class "Default")
      (node (ref "IC2") (pin "5") (pinfunction "EXTINT_5") (pintype "passive+no_connect"))
    )
    (net (code "93") (name "unconnected-(IC2-RESET_N-Pad9)") (class "Default")
      (node (ref "IC2") (pin "9") (pinfunction "RESET_N_9") (pintype "passive+no_connect"))
    )
    (net (code "94") (name "unconnected-(IC2-SAFEBOOT_N-Pad18)") (class "Default")
      (node (ref "IC2") (pin "18") (pinfunction "SAFEBOOT_N_18") (pintype "passive+no_connect"))
    )
    (net (code "95") (name "unconnected-(IC2-SCL-Pad17)") (class "Default")
      (node (ref "IC2") (pin "17") (pinfunction "SCL_17") (pintype "passive+no_connect"))
    )
    (net (code "96") (name "unconnected-(IC2-SDA-Pad16)") (class "Default")
      (node (ref "IC2") (pin "16") (pinfunction "SDA_16") (pintype "passive+no_connect"))
    )
    (net (code "97") (name "unconnected-(IC2-VCC_RF-Pad14)") (class "Default")
      (node (ref "IC2") (pin "14") (pinfunction "VCC_RF_14") (pintype "passive+no_connect"))
    )
    (net (code "98") (name "unconnected-(IC2-VIO_SEL-Pad15)") (class "Default")
      (node (ref "IC2") (pin "15") (pinfunction "VIO_SEL_15") (pintype "passive"))
    )
    (net (code "99") (name "unconnected-(IC2-V_IO-Pad7)") (class "Default")
      (node (ref "IC2") (pin "7") (pinfunction "V_IO_7") (pintype "passive"))
    )
    (net (code "100") (name "unconnected-(J4-VCC-Pad9)") (class "Default")
      (node (ref "J4") (pin "9") (pinfunction "VCC_9") (pintype "passive+no_connect"))
    )
    (net (code "101") (name "unconnected-(J6-SBU1-PadA8)") (class "Default")
      (node (ref "J6") (pin "A8") (pinfunction "SBU1_A8") (pintype "passive+no_connect"))
    )
    (net (code "102") (name "unconnected-(J6-SBU2-PadB8)") (class "Default")
      (node (ref "J6") (pin "B8") (pinfunction "SBU2_B8") (pintype "passive+no_connect"))
    )
    (net (code "103") (name "unconnected-(U5-CKO-Pad18)") (class "Default")
      (node (ref "U5") (pin "18") (pinfunction "CKO_18") (pintype "passive+no_connect"))
    )
    (net (code "104") (name "unconnected-(U5-GPIO0(MDC)-Pad48)") (class "Default")
      (node (ref "U5") (pin "48") (pinfunction "GPIO0(MDC)_48") (pintype "passive+no_connect"))
    )
    (net (code "105") (name "unconnected-(U5-GPIO1(MDIO)-Pad49)") (class "Default")
      (node (ref "U5") (pin "49") (pinfunction "GPIO1(MDIO)_49") (pintype "passive+no_connect"))
    )
    (net (code "106") (name "unconnected-(U5-GPIO2-Pad22)") (class "Default")
      (node (ref "U5") (pin "22") (pinfunction "GPIO2_22") (pintype "passive+no_connect"))
    )
    (net (code "107") (name "unconnected-(U5-GPIO15(1588_TOD)-Pad47)") (class "Default")
      (node (ref "U5") (pin "47") (pinfunction "GPIO15(1588_TOD)_47") (pintype "passive+no_connect"))
    )
    (net (code "108") (name "unconnected-(U5-LX-Pad60)") (class "Default")
      (node (ref "U5") (pin "60") (pinfunction "LX_60") (pintype "passive+no_connect"))
    )
  )
)
